# 00A-023_FRDM_Protoboard.net
KiCad netlist of a schematic drawn in EAGLE
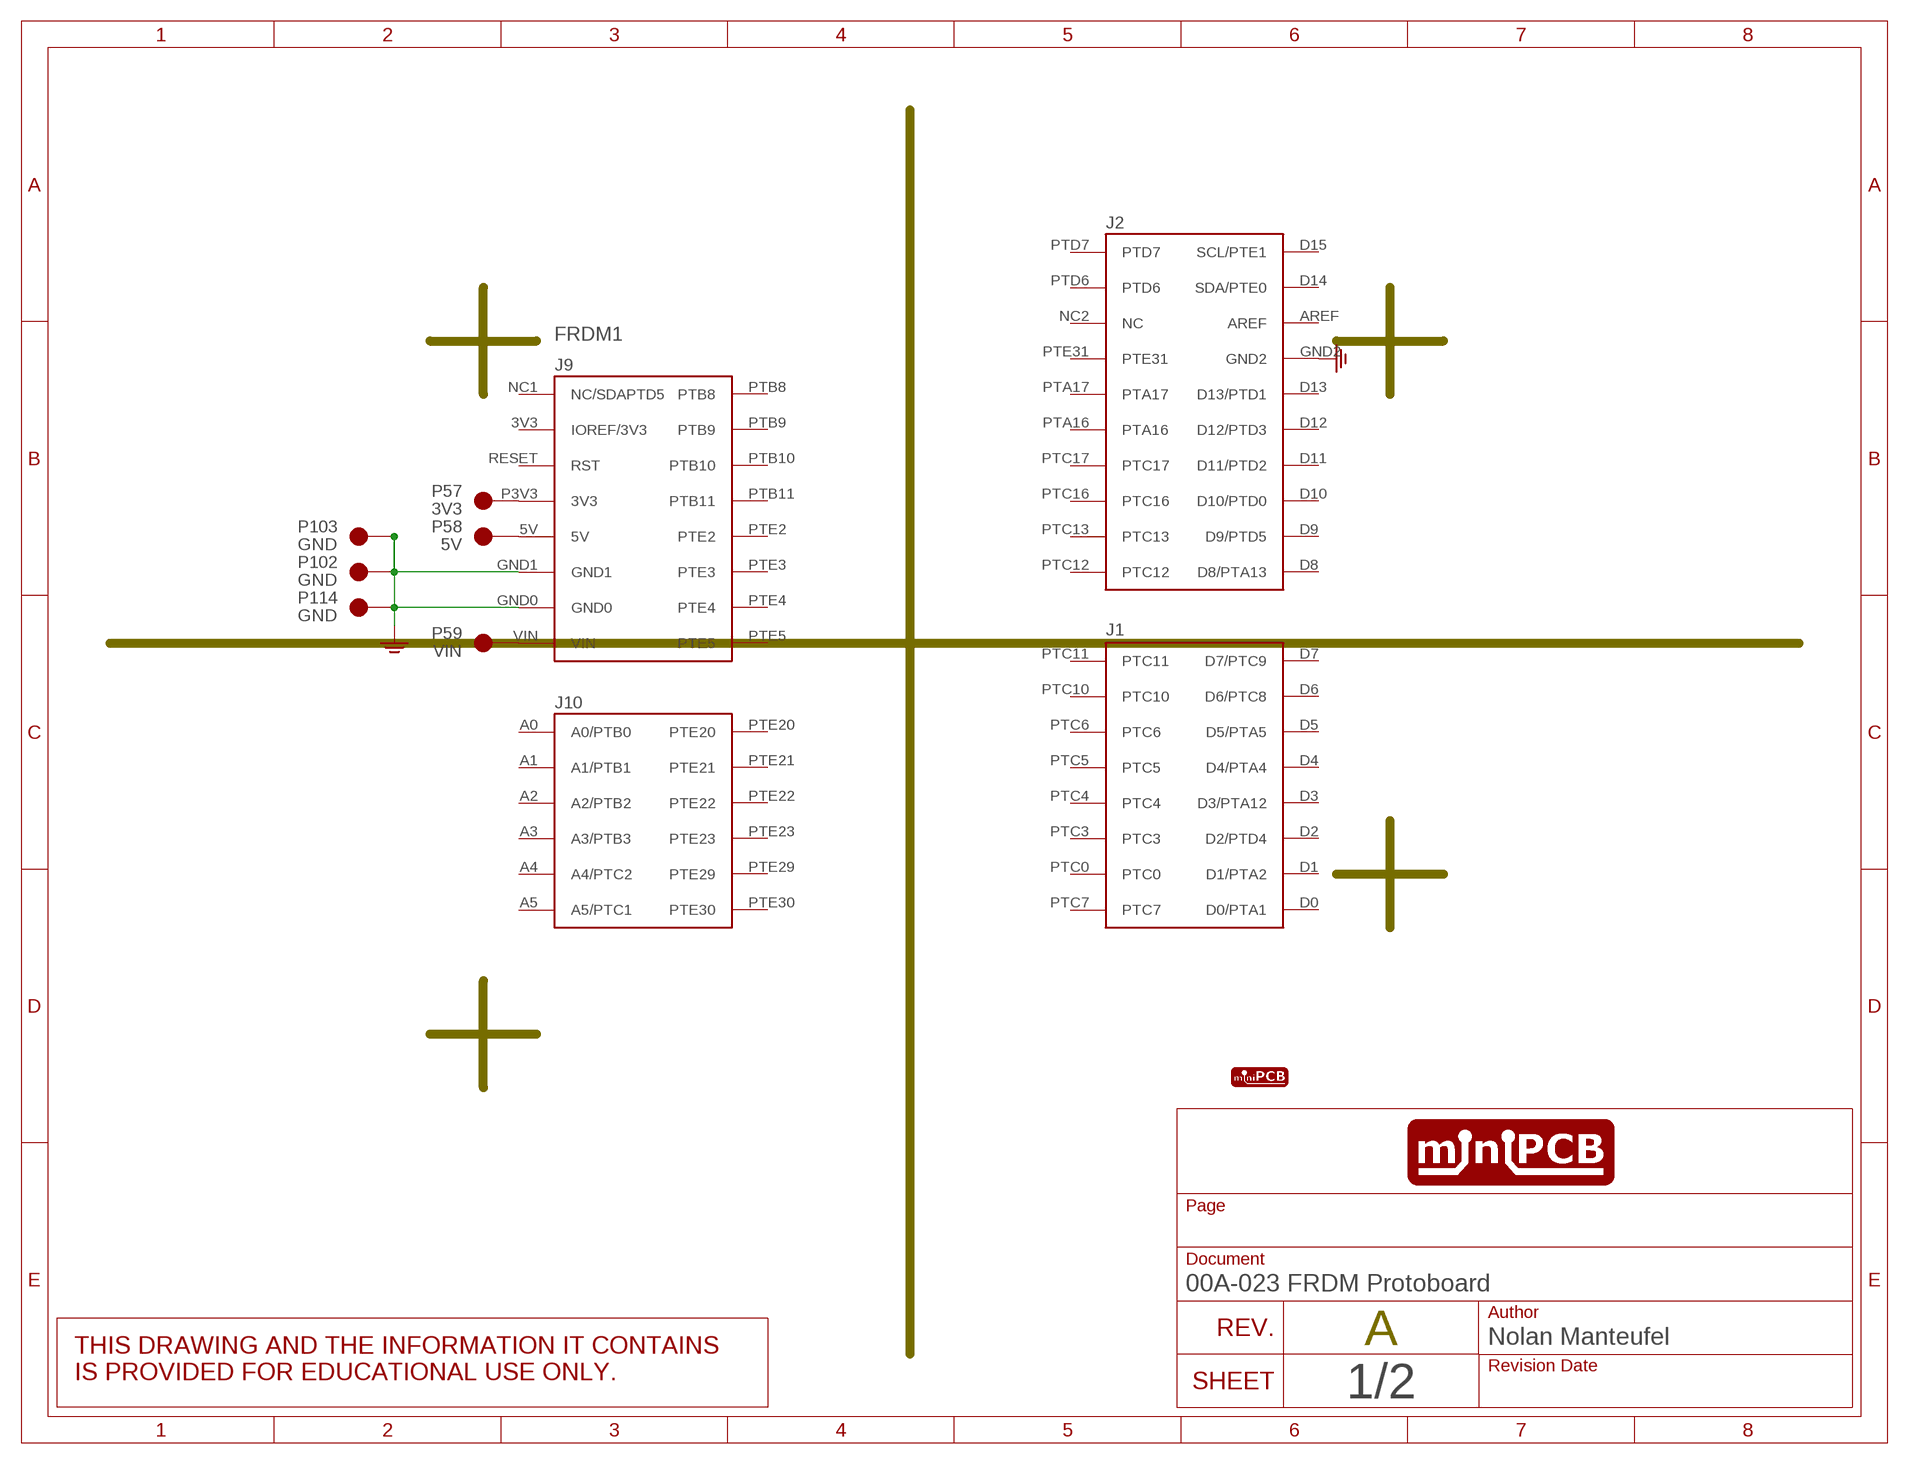
[diagram p0: schematic, sheet 1]
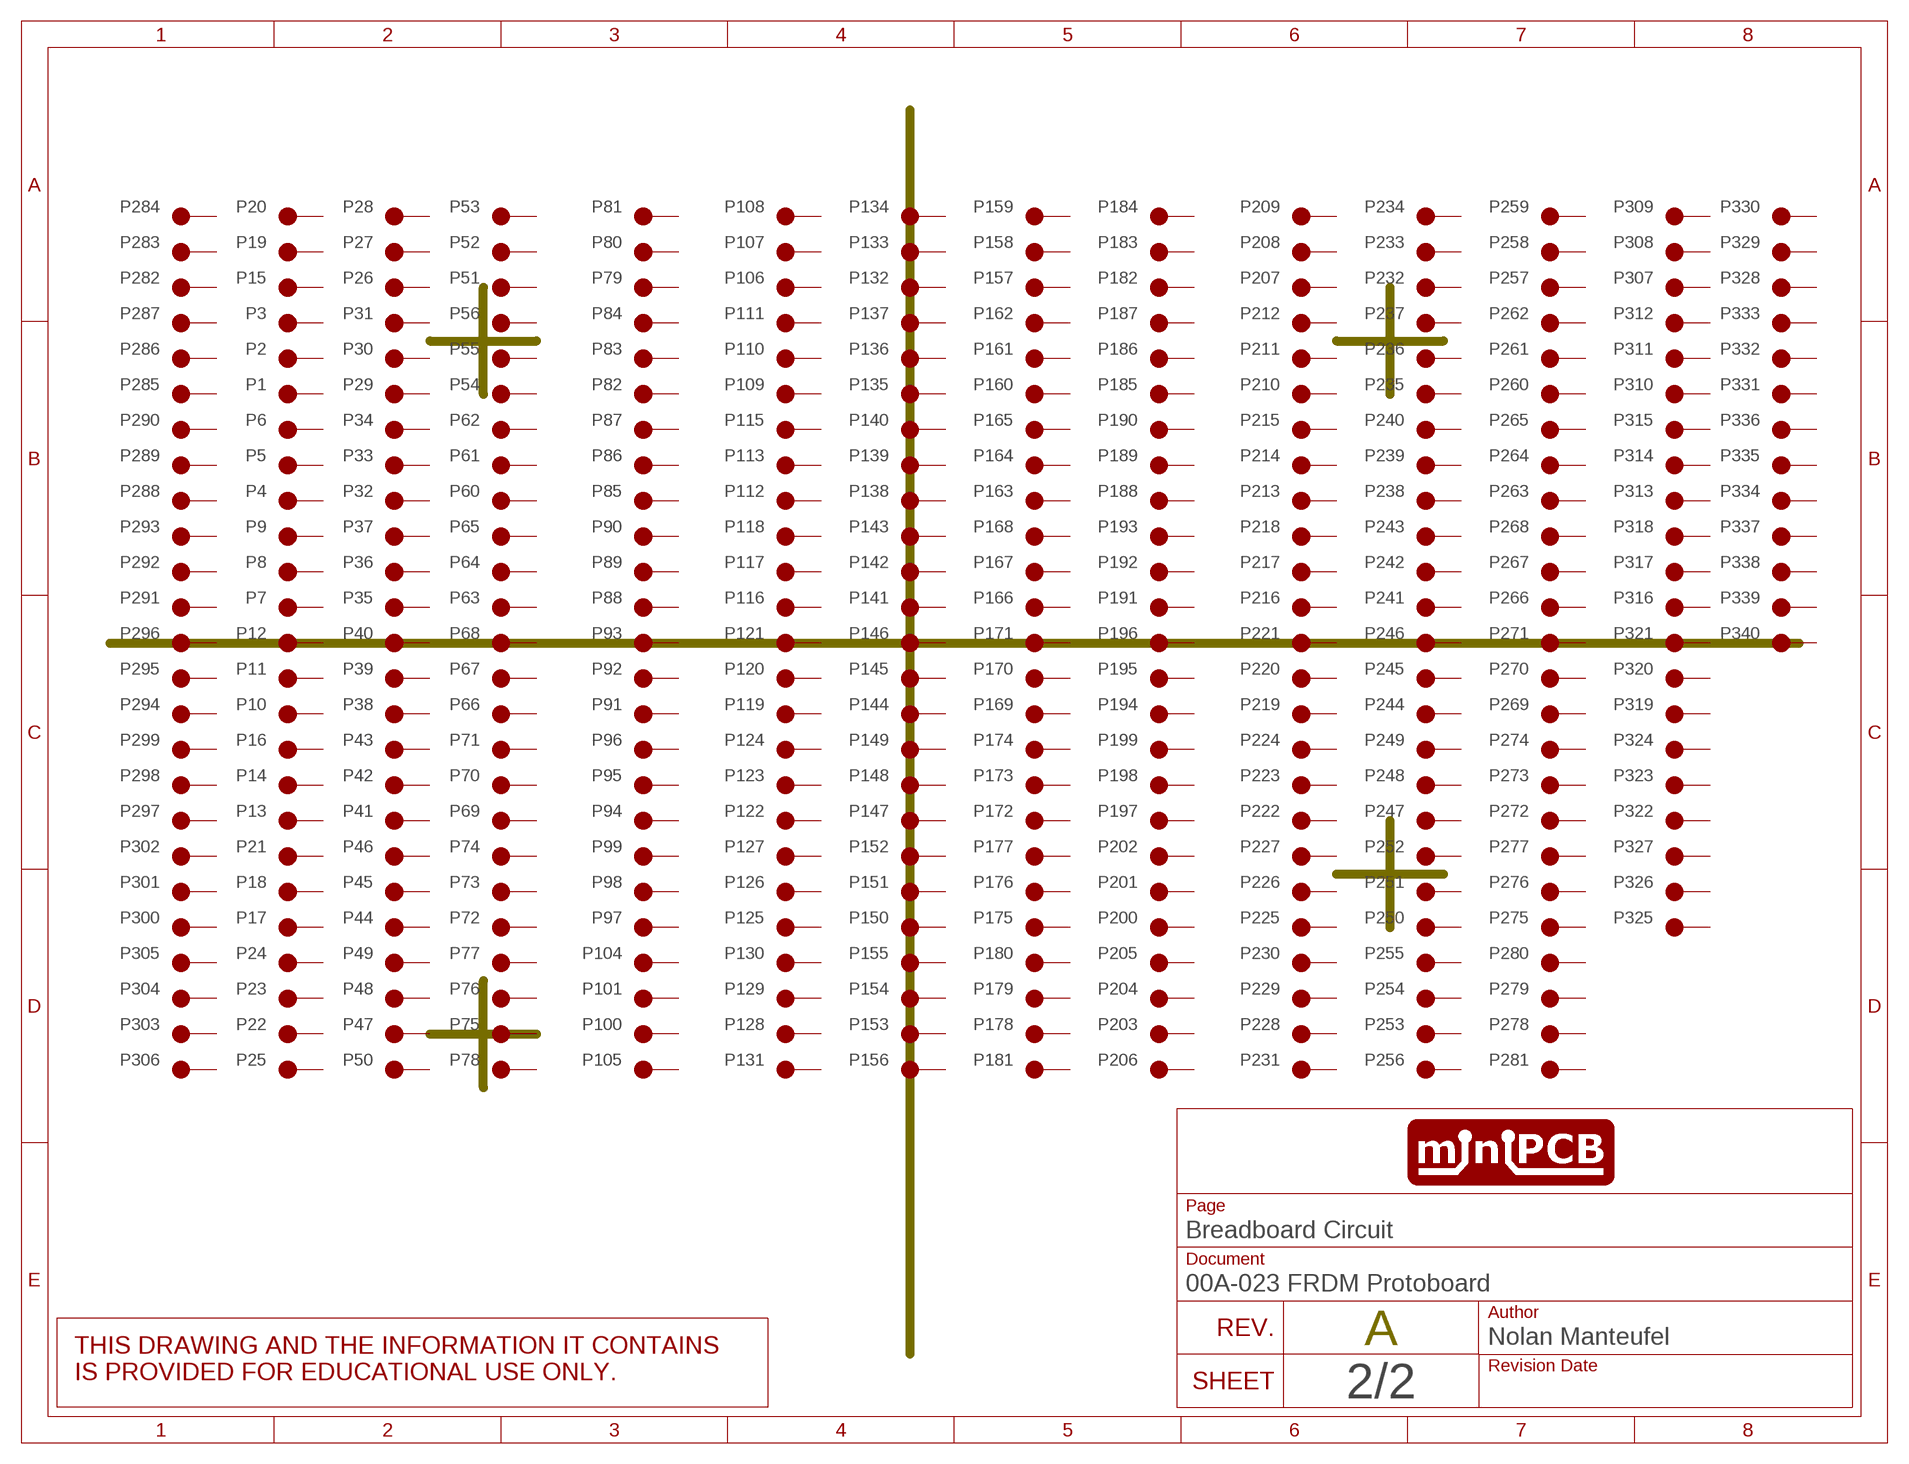
[diagram p1: schematic, sheet 2]

(export (version "E")
  (design (tool "Eeschema 10.0.6"))
  (components
    (comp (ref "P1")
      (value "PINS_11P_VALUE")
      (footprint "eagle-import:PINS_1-1P_VALUE")
      (libsource (lib "eagle-import") (part "PINS_11P_VALUE"))
    )
    (comp (ref "P2")
      (value "PINS_11P_VALUE")
      (footprint "eagle-import:PINS_1-1P_VALUE")
      (libsource (lib "eagle-import") (part "PINS_11P_VALUE"))
    )
    (comp (ref "P3")
      (value "PINS_11P_VALUE")
      (footprint "eagle-import:PINS_1-1P_VALUE")
      (libsource (lib "eagle-import") (part "PINS_11P_VALUE"))
    )
    (comp (ref "P4")
      (value "PINS_11P_VALUE")
      (footprint "eagle-import:PINS_1-1P_VALUE")
      (libsource (lib "eagle-import") (part "PINS_11P_VALUE"))
    )
    (comp (ref "P5")
      (value "PINS_11P_VALUE")
      (footprint "eagle-import:PINS_1-1P_VALUE")
      (libsource (lib "eagle-import") (part "PINS_11P_VALUE"))
    )
    (comp (ref "P6")
      (value "PINS_11P_VALUE")
      (footprint "eagle-import:PINS_1-1P_VALUE")
      (libsource (lib "eagle-import") (part "PINS_11P_VALUE"))
    )
    (comp (ref "P7")
      (value "PINS_11P_VALUE")
      (footprint "eagle-import:PINS_1-1P_VALUE")
      (libsource (lib "eagle-import") (part "PINS_11P_VALUE"))
    )
    (comp (ref "P8")
      (value "PINS_11P_VALUE")
      (footprint "eagle-import:PINS_1-1P_VALUE")
      (libsource (lib "eagle-import") (part "PINS_11P_VALUE"))
    )
    (comp (ref "P9")
      (value "PINS_11P_VALUE")
      (footprint "eagle-import:PINS_1-1P_VALUE")
      (libsource (lib "eagle-import") (part "PINS_11P_VALUE"))
    )
    (comp (ref "P10")
      (value "PINS_11P_VALUE")
      (footprint "eagle-import:PINS_1-1P_VALUE")
      (libsource (lib "eagle-import") (part "PINS_11P_VALUE"))
    )
    (comp (ref "P11")
      (value "PINS_11P_VALUE")
      (footprint "eagle-import:PINS_1-1P_VALUE")
      (libsource (lib "eagle-import") (part "PINS_11P_VALUE"))
    )
    (comp (ref "P12")
      (value "PINS_11P_VALUE")
      (footprint "eagle-import:PINS_1-1P_VALUE")
      (libsource (lib "eagle-import") (part "PINS_11P_VALUE"))
    )
    (comp (ref "P13")
      (value "PINS_11P_VALUE")
      (footprint "eagle-import:PINS_1-1P_VALUE")
      (libsource (lib "eagle-import") (part "PINS_11P_VALUE"))
    )
    (comp (ref "P14")
      (value "PINS_11P_VALUE")
      (footprint "eagle-import:PINS_1-1P_VALUE")
      (libsource (lib "eagle-import") (part "PINS_11P_VALUE"))
    )
    (comp (ref "P15")
      (value "PINS_11P_VALUE")
      (footprint "eagle-import:PINS_1-1P_VALUE")
      (libsource (lib "eagle-import") (part "PINS_11P_VALUE"))
    )
    (comp (ref "P16")
      (value "PINS_11P_VALUE")
      (footprint "eagle-import:PINS_1-1P_VALUE")
      (libsource (lib "eagle-import") (part "PINS_11P_VALUE"))
    )
    (comp (ref "P17")
      (value "PINS_11P_VALUE")
      (footprint "eagle-import:PINS_1-1P_VALUE")
      (libsource (lib "eagle-import") (part "PINS_11P_VALUE"))
    )
    (comp (ref "P18")
      (value "PINS_11P_VALUE")
      (footprint "eagle-import:PINS_1-1P_VALUE")
      (libsource (lib "eagle-import") (part "PINS_11P_VALUE"))
    )
    (comp (ref "P19")
      (value "PINS_11P_VALUE")
      (footprint "eagle-import:PINS_1-1P_VALUE")
      (libsource (lib "eagle-import") (part "PINS_11P_VALUE"))
    )
    (comp (ref "P20")
      (value "PINS_11P_VALUE")
      (footprint "eagle-import:PINS_1-1P_VALUE")
      (libsource (lib "eagle-import") (part "PINS_11P_VALUE"))
    )
    (comp (ref "P21")
      (value "PINS_11P_VALUE")
      (footprint "eagle-import:PINS_1-1P_VALUE")
      (libsource (lib "eagle-import") (part "PINS_11P_VALUE"))
    )
    (comp (ref "P22")
      (value "PINS_11P_VALUE")
      (footprint "eagle-import:PINS_1-1P_VALUE")
      (libsource (lib "eagle-import") (part "PINS_11P_VALUE"))
    )
    (comp (ref "P23")
      (value "PINS_11P_VALUE")
      (footprint "eagle-import:PINS_1-1P_VALUE")
      (libsource (lib "eagle-import") (part "PINS_11P_VALUE"))
    )
    (comp (ref "P24")
      (value "PINS_11P_VALUE")
      (footprint "eagle-import:PINS_1-1P_VALUE")
      (libsource (lib "eagle-import") (part "PINS_11P_VALUE"))
    )
    (comp (ref "P25")
      (value "PINS_11P_VALUE")
      (footprint "eagle-import:PINS_1-1P_VALUE")
      (libsource (lib "eagle-import") (part "PINS_11P_VALUE"))
    )
    (comp (ref "P26")
      (value "PINS_11P_VALUE")
      (footprint "eagle-import:PINS_1-1P_VALUE")
      (libsource (lib "eagle-import") (part "PINS_11P_VALUE"))
    )
    (comp (ref "P27")
      (value "PINS_11P_VALUE")
      (footprint "eagle-import:PINS_1-1P_VALUE")
      (libsource (lib "eagle-import") (part "PINS_11P_VALUE"))
    )
    (comp (ref "P28")
      (value "PINS_11P_VALUE")
      (footprint "eagle-import:PINS_1-1P_VALUE")
      (libsource (lib "eagle-import") (part "PINS_11P_VALUE"))
    )
    (comp (ref "P29")
      (value "PINS_11P_VALUE")
      (footprint "eagle-import:PINS_1-1P_VALUE")
      (libsource (lib "eagle-import") (part "PINS_11P_VALUE"))
    )
    (comp (ref "P30")
      (value "PINS_11P_VALUE")
      (footprint "eagle-import:PINS_1-1P_VALUE")
      (libsource (lib "eagle-import") (part "PINS_11P_VALUE"))
    )
    (comp (ref "P31")
      (value "PINS_11P_VALUE")
      (footprint "eagle-import:PINS_1-1P_VALUE")
      (libsource (lib "eagle-import") (part "PINS_11P_VALUE"))
    )
    (comp (ref "P32")
      (value "PINS_11P_VALUE")
      (footprint "eagle-import:PINS_1-1P_VALUE")
      (libsource (lib "eagle-import") (part "PINS_11P_VALUE"))
    )
    (comp (ref "P33")
      (value "PINS_11P_VALUE")
      (footprint "eagle-import:PINS_1-1P_VALUE")
      (libsource (lib "eagle-import") (part "PINS_11P_VALUE"))
    )
    (comp (ref "P34")
      (value "PINS_11P_VALUE")
      (footprint "eagle-import:PINS_1-1P_VALUE")
      (libsource (lib "eagle-import") (part "PINS_11P_VALUE"))
    )
    (comp (ref "P35")
      (value "PINS_11P_VALUE")
      (footprint "eagle-import:PINS_1-1P_VALUE")
      (libsource (lib "eagle-import") (part "PINS_11P_VALUE"))
    )
    (comp (ref "P36")
      (value "PINS_11P_VALUE")
      (footprint "eagle-import:PINS_1-1P_VALUE")
      (libsource (lib "eagle-import") (part "PINS_11P_VALUE"))
    )
    (comp (ref "P37")
      (value "PINS_11P_VALUE")
      (footprint "eagle-import:PINS_1-1P_VALUE")
      (libsource (lib "eagle-import") (part "PINS_11P_VALUE"))
    )
    (comp (ref "P38")
      (value "PINS_11P_VALUE")
      (footprint "eagle-import:PINS_1-1P_VALUE")
      (libsource (lib "eagle-import") (part "PINS_11P_VALUE"))
    )
    (comp (ref "P39")
      (value "PINS_11P_VALUE")
      (footprint "eagle-import:PINS_1-1P_VALUE")
      (libsource (lib "eagle-import") (part "PINS_11P_VALUE"))
    )
    (comp (ref "P40")
      (value "PINS_11P_VALUE")
      (footprint "eagle-import:PINS_1-1P_VALUE")
      (libsource (lib "eagle-import") (part "PINS_11P_VALUE"))
    )
    (comp (ref "P41")
      (value "PINS_11P_VALUE")
      (footprint "eagle-import:PINS_1-1P_VALUE")
      (libsource (lib "eagle-import") (part "PINS_11P_VALUE"))
    )
    (comp (ref "P42")
      (value "PINS_11P_VALUE")
      (footprint "eagle-import:PINS_1-1P_VALUE")
      (libsource (lib "eagle-import") (part "PINS_11P_VALUE"))
    )
    (comp (ref "P43")
      (value "PINS_11P_VALUE")
      (footprint "eagle-import:PINS_1-1P_VALUE")
      (libsource (lib "eagle-import") (part "PINS_11P_VALUE"))
    )
    (comp (ref "P44")
      (value "PINS_11P_VALUE")
      (footprint "eagle-import:PINS_1-1P_VALUE")
      (libsource (lib "eagle-import") (part "PINS_11P_VALUE"))
    )
    (comp (ref "P45")
      (value "PINS_11P_VALUE")
      (footprint "eagle-import:PINS_1-1P_VALUE")
      (libsource (lib "eagle-import") (part "PINS_11P_VALUE"))
    )
    (comp (ref "P46")
      (value "PINS_11P_VALUE")
      (footprint "eagle-import:PINS_1-1P_VALUE")
      (libsource (lib "eagle-import") (part "PINS_11P_VALUE"))
    )
    (comp (ref "P47")
      (value "PINS_11P_VALUE")
      (footprint "eagle-import:PINS_1-1P_VALUE")
      (libsource (lib "eagle-import") (part "PINS_11P_VALUE"))
    )
    (comp (ref "P48")
      (value "PINS_11P_VALUE")
      (footprint "eagle-import:PINS_1-1P_VALUE")
      (libsource (lib "eagle-import") (part "PINS_11P_VALUE"))
    )
    (comp (ref "P49")
      (value "PINS_11P_VALUE")
      (footprint "eagle-import:PINS_1-1P_VALUE")
      (libsource (lib "eagle-import") (part "PINS_11P_VALUE"))
    )
    (comp (ref "P50")
      (value "PINS_11P_VALUE")
      (footprint "eagle-import:PINS_1-1P_VALUE")
      (libsource (lib "eagle-import") (part "PINS_11P_VALUE"))
    )
    (comp (ref "P51")
      (value "PINS_11P_VALUE")
      (footprint "eagle-import:PINS_1-1P_VALUE")
      (libsource (lib "eagle-import") (part "PINS_11P_VALUE"))
    )
    (comp (ref "P52")
      (value "PINS_11P_VALUE")
      (footprint "eagle-import:PINS_1-1P_VALUE")
      (libsource (lib "eagle-import") (part "PINS_11P_VALUE"))
    )
    (comp (ref "P53")
      (value "PINS_11P_VALUE")
      (footprint "eagle-import:PINS_1-1P_VALUE")
      (libsource (lib "eagle-import") (part "PINS_11P_VALUE"))
    )
    (comp (ref "P54")
      (value "PINS_11P_VALUE")
      (footprint "eagle-import:PINS_1-1P_VALUE")
      (libsource (lib "eagle-import") (part "PINS_11P_VALUE"))
    )
    (comp (ref "P55")
      (value "PINS_11P_VALUE")
      (footprint "eagle-import:PINS_1-1P_VALUE")
      (libsource (lib "eagle-import") (part "PINS_11P_VALUE"))
    )
    (comp (ref "P56")
      (value "PINS_11P_VALUE")
      (footprint "eagle-import:PINS_1-1P_VALUE")
      (libsource (lib "eagle-import") (part "PINS_11P_VALUE"))
    )
    (comp (ref "P60")
      (value "PINS_11P_VALUE")
      (footprint "eagle-import:PINS_1-1P_VALUE")
      (libsource (lib "eagle-import") (part "PINS_11P_VALUE"))
    )
    (comp (ref "P61")
      (value "PINS_11P_VALUE")
      (footprint "eagle-import:PINS_1-1P_VALUE")
      (libsource (lib "eagle-import") (part "PINS_11P_VALUE"))
    )
    (comp (ref "P62")
      (value "PINS_11P_VALUE")
      (footprint "eagle-import:PINS_1-1P_VALUE")
      (libsource (lib "eagle-import") (part "PINS_11P_VALUE"))
    )
    (comp (ref "P63")
      (value "PINS_11P_VALUE")
      (footprint "eagle-import:PINS_1-1P_VALUE")
      (libsource (lib "eagle-import") (part "PINS_11P_VALUE"))
    )
    (comp (ref "P64")
      (value "PINS_11P_VALUE")
      (footprint "eagle-import:PINS_1-1P_VALUE")
      (libsource (lib "eagle-import") (part "PINS_11P_VALUE"))
    )
    (comp (ref "P65")
      (value "PINS_11P_VALUE")
      (footprint "eagle-import:PINS_1-1P_VALUE")
      (libsource (lib "eagle-import") (part "PINS_11P_VALUE"))
    )
    (comp (ref "P66")
      (value "PINS_11P_VALUE")
      (footprint "eagle-import:PINS_1-1P_VALUE")
      (libsource (lib "eagle-import") (part "PINS_11P_VALUE"))
    )
    (comp (ref "P67")
      (value "PINS_11P_VALUE")
      (footprint "eagle-import:PINS_1-1P_VALUE")
      (libsource (lib "eagle-import") (part "PINS_11P_VALUE"))
    )
    (comp (ref "P68")
      (value "PINS_11P_VALUE")
      (footprint "eagle-import:PINS_1-1P_VALUE")
      (libsource (lib "eagle-import") (part "PINS_11P_VALUE"))
    )
    (comp (ref "P69")
      (value "PINS_11P_VALUE")
      (footprint "eagle-import:PINS_1-1P_VALUE")
      (libsource (lib "eagle-import") (part "PINS_11P_VALUE"))
    )
    (comp (ref "P70")
      (value "PINS_11P_VALUE")
      (footprint "eagle-import:PINS_1-1P_VALUE")
      (libsource (lib "eagle-import") (part "PINS_11P_VALUE"))
    )
    (comp (ref "P71")
      (value "PINS_11P_VALUE")
      (footprint "eagle-import:PINS_1-1P_VALUE")
      (libsource (lib "eagle-import") (part "PINS_11P_VALUE"))
    )
    (comp (ref "P72")
      (value "PINS_11P_VALUE")
      (footprint "eagle-import:PINS_1-1P_VALUE")
      (libsource (lib "eagle-import") (part "PINS_11P_VALUE"))
    )
    (comp (ref "P73")
      (value "PINS_11P_VALUE")
      (footprint "eagle-import:PINS_1-1P_VALUE")
      (libsource (lib "eagle-import") (part "PINS_11P_VALUE"))
    )
    (comp (ref "P74")
      (value "PINS_11P_VALUE")
      (footprint "eagle-import:PINS_1-1P_VALUE")
      (libsource (lib "eagle-import") (part "PINS_11P_VALUE"))
    )
    (comp (ref "P75")
      (value "PINS_11P_VALUE")
      (footprint "eagle-import:PINS_1-1P_VALUE")
      (libsource (lib "eagle-import") (part "PINS_11P_VALUE"))
    )
    (comp (ref "P76")
      (value "PINS_11P_VALUE")
      (footprint "eagle-import:PINS_1-1P_VALUE")
      (libsource (lib "eagle-import") (part "PINS_11P_VALUE"))
    )
    (comp (ref "P77")
      (value "PINS_11P_VALUE")
      (footprint "eagle-import:PINS_1-1P_VALUE")
      (libsource (lib "eagle-import") (part "PINS_11P_VALUE"))
    )
    (comp (ref "P78")
      (value "PINS_11P_VALUE")
      (footprint "eagle-import:PINS_1-1P_VALUE")
      (libsource (lib "eagle-import") (part "PINS_11P_VALUE"))
    )
    (comp (ref "P79")
      (value "PINS_11P_VALUE")
      (footprint "eagle-import:PINS_1-1P_VALUE")
      (libsource (lib "eagle-import") (part "PINS_11P_VALUE"))
    )
    (comp (ref "P80")
      (value "PINS_11P_VALUE")
      (footprint "eagle-import:PINS_1-1P_VALUE")
      (libsource (lib "eagle-import") (part "PINS_11P_VALUE"))
    )
    (comp (ref "P81")
      (value "PINS_11P_VALUE")
      (footprint "eagle-import:PINS_1-1P_VALUE")
      (libsource (lib "eagle-import") (part "PINS_11P_VALUE"))
    )
    (comp (ref "P82")
      (value "PINS_11P_VALUE")
      (footprint "eagle-import:PINS_1-1P_VALUE")
      (libsource (lib "eagle-import") (part "PINS_11P_VALUE"))
    )
    (comp (ref "P83")
      (value "PINS_11P_VALUE")
      (footprint "eagle-import:PINS_1-1P_VALUE")
      (libsource (lib "eagle-import") (part "PINS_11P_VALUE"))
    )
    (comp (ref "P84")
      (value "PINS_11P_VALUE")
      (footprint "eagle-import:PINS_1-1P_VALUE")
      (libsource (lib "eagle-import") (part "PINS_11P_VALUE"))
    )
    (comp (ref "P85")
      (value "PINS_11P_VALUE")
      (footprint "eagle-import:PINS_1-1P_VALUE")
      (libsource (lib "eagle-import") (part "PINS_11P_VALUE"))
    )
    (comp (ref "P86")
      (value "PINS_11P_VALUE")
      (footprint "eagle-import:PINS_1-1P_VALUE")
      (libsource (lib "eagle-import") (part "PINS_11P_VALUE"))
    )
    (comp (ref "P87")
      (value "PINS_11P_VALUE")
      (footprint "eagle-import:PINS_1-1P_VALUE")
      (libsource (lib "eagle-import") (part "PINS_11P_VALUE"))
    )
    (comp (ref "P88")
      (value "PINS_11P_VALUE")
      (footprint "eagle-import:PINS_1-1P_VALUE")
      (libsource (lib "eagle-import") (part "PINS_11P_VALUE"))
    )
    (comp (ref "P89")
      (value "PINS_11P_VALUE")
      (footprint "eagle-import:PINS_1-1P_VALUE")
      (libsource (lib "eagle-import") (part "PINS_11P_VALUE"))
    )
    (comp (ref "P90")
      (value "PINS_11P_VALUE")
      (footprint "eagle-import:PINS_1-1P_VALUE")
      (libsource (lib "eagle-import") (part "PINS_11P_VALUE"))
    )
    (comp (ref "P91")
      (value "PINS_11P_VALUE")
      (footprint "eagle-import:PINS_1-1P_VALUE")
      (libsource (lib "eagle-import") (part "PINS_11P_VALUE"))
    )
    (comp (ref "P92")
      (value "PINS_11P_VALUE")
      (footprint "eagle-import:PINS_1-1P_VALUE")
      (libsource (lib "eagle-import") (part "PINS_11P_VALUE"))
    )
    (comp (ref "P93")
      (value "PINS_11P_VALUE")
      (footprint "eagle-import:PINS_1-1P_VALUE")
      (libsource (lib "eagle-import") (part "PINS_11P_VALUE"))
    )
    (comp (ref "P94")
      (value "PINS_11P_VALUE")
      (footprint "eagle-import:PINS_1-1P_VALUE")
      (libsource (lib "eagle-import") (part "PINS_11P_VALUE"))
    )
    (comp (ref "P95")
      (value "PINS_11P_VALUE")
      (footprint "eagle-import:PINS_1-1P_VALUE")
      (libsource (lib "eagle-import") (part "PINS_11P_VALUE"))
    )
    (comp (ref "P96")
      (value "PINS_11P_VALUE")
      (footprint "eagle-import:PINS_1-1P_VALUE")
      (libsource (lib "eagle-import") (part "PINS_11P_VALUE"))
    )
    (comp (ref "P97")
      (value "PINS_11P_VALUE")
      (footprint "eagle-import:PINS_1-1P_VALUE")
      (libsource (lib "eagle-import") (part "PINS_11P_VALUE"))
    )
    (comp (ref "P98")
      (value "PINS_11P_VALUE")
      (footprint "eagle-import:PINS_1-1P_VALUE")
      (libsource (lib "eagle-import") (part "PINS_11P_VALUE"))
    )
    (comp (ref "P99")
      (value "PINS_11P_VALUE")
      (footprint "eagle-import:PINS_1-1P_VALUE")
      (libsource (lib "eagle-import") (part "PINS_11P_VALUE"))
    )
    (comp (ref "P100")
      (value "PINS_11P_VALUE")
      (footprint "eagle-import:PINS_1-1P_VALUE")
      (libsource (lib "eagle-import") (part "PINS_11P_VALUE"))
    )
    (comp (ref "P101")
      (value "PINS_11P_VALUE")
      (footprint "eagle-import:PINS_1-1P_VALUE")
      (libsource (lib "eagle-import") (part "PINS_11P_VALUE"))
    )
    (comp (ref "P104")
      (value "PINS_11P_VALUE")
      (footprint "eagle-import:PINS_1-1P_VALUE")
      (libsource (lib "eagle-import") (part "PINS_11P_VALUE"))
    )
    (comp (ref "P105")
      (value "PINS_11P_VALUE")
      (footprint "eagle-import:PINS_1-1P_VALUE")
      (libsource (lib "eagle-import") (part "PINS_11P_VALUE"))
    )
    (comp (ref "P106")
      (value "PINS_11P_VALUE")
      (footprint "eagle-import:PINS_1-1P_VALUE")
      (libsource (lib "eagle-import") (part "PINS_11P_VALUE"))
    )
    (comp (ref "P107")
      (value "PINS_11P_VALUE")
      (footprint "eagle-import:PINS_1-1P_VALUE")
      (libsource (lib "eagle-import") (part "PINS_11P_VALUE"))
    )
    (comp (ref "P108")
      (value "PINS_11P_VALUE")
      (footprint "eagle-import:PINS_1-1P_VALUE")
      (libsource (lib "eagle-import") (part "PINS_11P_VALUE"))
    )
    (comp (ref "P109")
      (value "PINS_11P_VALUE")
      (footprint "eagle-import:PINS_1-1P_VALUE")
      (libsource (lib "eagle-import") (part "PINS_11P_VALUE"))
    )
    (comp (ref "P110")
      (value "PINS_11P_VALUE")
      (footprint "eagle-import:PINS_1-1P_VALUE")
      (libsource (lib "eagle-import") (part "PINS_11P_VALUE"))
    )
    (comp (ref "P111")
      (value "PINS_11P_VALUE")
      (footprint "eagle-import:PINS_1-1P_VALUE")
      (libsource (lib "eagle-import") (part "PINS_11P_VALUE"))
    )
    (comp (ref "P112")
      (value "PINS_11P_VALUE")
      (footprint "eagle-import:PINS_1-1P_VALUE")
      (libsource (lib "eagle-import") (part "PINS_11P_VALUE"))
    )
    (comp (ref "P113")
      (value "PINS_11P_VALUE")
      (footprint "eagle-import:PINS_1-1P_VALUE")
      (libsource (lib "eagle-import") (part "PINS_11P_VALUE"))
    )
    (comp (ref "P115")
      (value "PINS_11P_VALUE")
      (footprint "eagle-import:PINS_1-1P_VALUE")
      (libsource (lib "eagle-import") (part "PINS_11P_VALUE"))
    )
    (comp (ref "P116")
      (value "PINS_11P_VALUE")
      (footprint "eagle-import:PINS_1-1P_VALUE")
      (libsource (lib "eagle-import") (part "PINS_11P_VALUE"))
    )
    (comp (ref "P117")
      (value "PINS_11P_VALUE")
      (footprint "eagle-import:PINS_1-1P_VALUE")
      (libsource (lib "eagle-import") (part "PINS_11P_VALUE"))
    )
    (comp (ref "P118")
      (value "PINS_11P_VALUE")
      (footprint "eagle-import:PINS_1-1P_VALUE")
      (libsource (lib "eagle-import") (part "PINS_11P_VALUE"))
    )
    (comp (ref "P119")
      (value "PINS_11P_VALUE")
      (footprint "eagle-import:PINS_1-1P_VALUE")
      (libsource (lib "eagle-import") (part "PINS_11P_VALUE"))
    )
    (comp (ref "P120")
      (value "PINS_11P_VALUE")
      (footprint "eagle-import:PINS_1-1P_VALUE")
      (libsource (lib "eagle-import") (part "PINS_11P_VALUE"))
    )
    (comp (ref "P121")
      (value "PINS_11P_VALUE")
      (footprint "eagle-import:PINS_1-1P_VALUE")
      (libsource (lib "eagle-import") (part "PINS_11P_VALUE"))
    )
    (comp (ref "P122")
      (value "PINS_11P_VALUE")
      (footprint "eagle-import:PINS_1-1P_VALUE")
      (libsource (lib "eagle-import") (part "PINS_11P_VALUE"))
    )
    (comp (ref "P123")
      (value "PINS_11P_VALUE")
      (footprint "eagle-import:PINS_1-1P_VALUE")
      (libsource (lib "eagle-import") (part "PINS_11P_VALUE"))
    )
    (comp (ref "P124")
      (value "PINS_11P_VALUE")
      (footprint "eagle-import:PINS_1-1P_VALUE")
      (libsource (lib "eagle-import") (part "PINS_11P_VALUE"))
    )
    (comp (ref "P125")
      (value "PINS_11P_VALUE")
      (footprint "eagle-import:PINS_1-1P_VALUE")
      (libsource (lib "eagle-import") (part "PINS_11P_VALUE"))
    )
    (comp (ref "P126")
      (value "PINS_11P_VALUE")
      (footprint "eagle-import:PINS_1-1P_VALUE")
      (libsource (lib "eagle-import") (part "PINS_11P_VALUE"))
    )
    (comp (ref "P127")
      (value "PINS_11P_VALUE")
      (footprint "eagle-import:PINS_1-1P_VALUE")
      (libsource (lib "eagle-import") (part "PINS_11P_VALUE"))
    )
    (comp (ref "P128")
      (value "PINS_11P_VALUE")
      (footprint "eagle-import:PINS_1-1P_VALUE")
      (libsource (lib "eagle-import") (part "PINS_11P_VALUE"))
    )
    (comp (ref "P129")
      (value "PINS_11P_VALUE")
      (footprint "eagle-import:PINS_1-1P_VALUE")
      (libsource (lib "eagle-import") (part "PINS_11P_VALUE"))
    )
    (comp (ref "P130")
      (value "PINS_11P_VALUE")
      (footprint "eagle-import:PINS_1-1P_VALUE")
      (libsource (lib "eagle-import") (part "PINS_11P_VALUE"))
    )
    (comp (ref "P131")
      (value "PINS_11P_VALUE")
      (footprint "eagle-import:PINS_1-1P_VALUE")
      (libsource (lib "eagle-import") (part "PINS_11P_VALUE"))
    )
    (comp (ref "P132")
      (value "PINS_11P_VALUE")
      (footprint "eagle-import:PINS_1-1P_VALUE")
      (libsource (lib "eagle-import") (part "PINS_11P_VALUE"))
    )
    (comp (ref "P133")
      (value "PINS_11P_VALUE")
      (footprint "eagle-import:PINS_1-1P_VALUE")
      (libsource (lib "eagle-import") (part "PINS_11P_VALUE"))
    )
    (comp (ref "P134")
      (value "PINS_11P_VALUE")
      (footprint "eagle-import:PINS_1-1P_VALUE")
      (libsource (lib "eagle-import") (part "PINS_11P_VALUE"))
    )
    (comp (ref "P135")
      (value "PINS_11P_VALUE")
      (footprint "eagle-import:PINS_1-1P_VALUE")
      (libsource (lib "eagle-import") (part "PINS_11P_VALUE"))
    )
    (comp (ref "P136")
      (value "PINS_11P_VALUE")
      (footprint "eagle-import:PINS_1-1P_VALUE")
      (libsource (lib "eagle-import") (part "PINS_11P_VALUE"))
    )
    (comp (ref "P137")
      (value "PINS_11P_VALUE")
      (footprint "eagle-import:PINS_1-1P_VALUE")
      (libsource (lib "eagle-import") (part "PINS_11P_VALUE"))
    )
    (comp (ref "P138")
      (value "PINS_11P_VALUE")
      (footprint "eagle-import:PINS_1-1P_VALUE")
      (libsource (lib "eagle-import") (part "PINS_11P_VALUE"))
    )
    (comp (ref "P139")
      (value "PINS_11P_VALUE")
      (footprint "eagle-import:PINS_1-1P_VALUE")
      (libsource (lib "eagle-import") (part "PINS_11P_VALUE"))
    )
    (comp (ref "P140")
      (value "PINS_11P_VALUE")
      (footprint "eagle-import:PINS_1-1P_VALUE")
      (libsource (lib "eagle-import") (part "PINS_11P_VALUE"))
    )
    (comp (ref "P141")
      (value "PINS_11P_VALUE")
      (footprint "eagle-import:PINS_1-1P_VALUE")
      (libsource (lib "eagle-import") (part "PINS_11P_VALUE"))
    )
    (comp (ref "P142")
      (value "PINS_11P_VALUE")
      (footprint "eagle-import:PINS_1-1P_VALUE")
      (libsource (lib "eagle-import") (part "PINS_11P_VALUE"))
    )
    (comp (ref "P143")
      (value "PINS_11P_VALUE")
      (footprint "eagle-import:PINS_1-1P_VALUE")
      (libsource (lib "eagle-import") (part "PINS_11P_VALUE"))
    )
    (comp (ref "P144")
      (value "PINS_11P_VALUE")
      (footprint "eagle-import:PINS_1-1P_VALUE")
      (libsource (lib "eagle-import") (part "PINS_11P_VALUE"))
    )
    (comp (ref "P145")
      (value "PINS_11P_VALUE")
      (footprint "eagle-import:PINS_1-1P_VALUE")
      (libsource (lib "eagle-import") (part "PINS_11P_VALUE"))
    )
    (comp (ref "P146")
      (value "PINS_11P_VALUE")
      (footprint "eagle-import:PINS_1-1P_VALUE")
      (libsource (lib "eagle-import") (part "PINS_11P_VALUE"))
    )
    (comp (ref "P147")
      (value "PINS_11P_VALUE")
      (footprint "eagle-import:PINS_1-1P_VALUE")
      (libsource (lib "eagle-import") (part "PINS_11P_VALUE"))
    )
    (comp (ref "P148")
      (value "PINS_11P_VALUE")
      (footprint "eagle-import:PINS_1-1P_VALUE")
      (libsource (lib "eagle-import") (part "PINS_11P_VALUE"))
    )
    (comp (ref "P149")
      (value "PINS_11P_VALUE")
      (footprint "eagle-import:PINS_1-1P_VALUE")
      (libsource (lib "eagle-import") (part "PINS_11P_VALUE"))
    )
    (comp (ref "P150")
      (value "PINS_11P_VALUE")
      (footprint "eagle-import:PINS_1-1P_VALUE")
      (libsource (lib "eagle-import") (part "PINS_11P_VALUE"))
    )
    (comp (ref "P151")
      (value "PINS_11P_VALUE")
      (footprint "eagle-import:PINS_1-1P_VALUE")
      (libsource (lib "eagle-import") (part "PINS_11P_VALUE"))
    )
    (comp (ref "P152")
      (value "PINS_11P_VALUE")
      (footprint "eagle-import:PINS_1-1P_VALUE")
      (libsource (lib "eagle-import") (part "PINS_11P_VALUE"))
    )
    (comp (ref "P153")
      (value "PINS_11P_VALUE")
      (footprint "eagle-import:PINS_1-1P_VALUE")
      (libsource (lib "eagle-import") (part "PINS_11P_VALUE"))
    )
    (comp (ref "P154")
      (value "PINS_11P_VALUE")
      (footprint "eagle-import:PINS_1-1P_VALUE")
      (libsource (lib "eagle-import") (part "PINS_11P_VALUE"))
    )
    (comp (ref "P155")
      (value "PINS_11P_VALUE")
      (footprint "eagle-import:PINS_1-1P_VALUE")
      (libsource (lib "eagle-import") (part "PINS_11P_VALUE"))
    )
    (comp (ref "P156")
      (value "PINS_11P_VALUE")
      (footprint "eagle-import:PINS_1-1P_VALUE")
      (libsource (lib "eagle-import") (part "PINS_11P_VALUE"))
    )
    (comp (ref "P157")
      (value "PINS_11P_VALUE")
      (footprint "eagle-import:PINS_1-1P_VALUE")
      (libsource (lib "eagle-import") (part "PINS_11P_VALUE"))
    )
    (comp (ref "P158")
      (value "PINS_11P_VALUE")
      (footprint "eagle-import:PINS_1-1P_VALUE")
      (libsource (lib "eagle-import") (part "PINS_11P_VALUE"))
    )
    (comp (ref "P159")
      (value "PINS_11P_VALUE")
      (footprint "eagle-import:PINS_1-1P_VALUE")
      (libsource (lib "eagle-import") (part "PINS_11P_VALUE"))
    )
    (comp (ref "P160")
      (value "PINS_11P_VALUE")
      (footprint "eagle-import:PINS_1-1P_VALUE")
      (libsource (lib "eagle-import") (part "PINS_11P_VALUE"))
    )
    (comp (ref "P161")
      (value "PINS_11P_VALUE")
      (footprint "eagle-import:PINS_1-1P_VALUE")
      (libsource (lib "eagle-import") (part "PINS_11P_VALUE"))
    )
    (comp (ref "P162")
      (value "PINS_11P_VALUE")
      (footprint "eagle-import:PINS_1-1P_VALUE")
      (libsource (lib "eagle-import") (part "PINS_11P_VALUE"))
    )
    (comp (ref "P163")
      (value "PINS_11P_VALUE")
      (footprint "eagle-import:PINS_1-1P_VALUE")
      (libsource (lib "eagle-import") (part "PINS_11P_VALUE"))
    )
    (comp (ref "P164")
      (value "PINS_11P_VALUE")
      (footprint "eagle-import:PINS_1-1P_VALUE")
      (libsource (lib "eagle-import") (part "PINS_11P_VALUE"))
    )
    (comp (ref "P165")
      (value "PINS_11P_VALUE")
      (footprint "eagle-import:PINS_1-1P_VALUE")
      (libsource (lib "eagle-import") (part "PINS_11P_VALUE"))
    )
    (comp (ref "P166")
      (value "PINS_11P_VALUE")
      (footprint "eagle-import:PINS_1-1P_VALUE")
      (libsource (lib "eagle-import") (part "PINS_11P_VALUE"))
    )
    (comp (ref "P167")
      (value "PINS_11P_VALUE")
      (footprint "eagle-import:PINS_1-1P_VALUE")
      (libsource (lib "eagle-import") (part "PINS_11P_VALUE"))
    )
    (comp (ref "P168")
      (value "PINS_11P_VALUE")
      (footprint "eagle-import:PINS_1-1P_VALUE")
      (libsource (lib "eagle-import") (part "PINS_11P_VALUE"))
    )
    (comp (ref "P169")
      (value "PINS_11P_VALUE")
      (footprint "eagle-import:PINS_1-1P_VALUE")
      (libsource (lib "eagle-import") (part "PINS_11P_VALUE"))
    )
    (comp (ref "P170")
      (value "PINS_11P_VALUE")
      (footprint "eagle-import:PINS_1-1P_VALUE")
      (libsource (lib "eagle-import") (part "PINS_11P_VALUE"))
    )
    (comp (ref "P171")
      (value "PINS_11P_VALUE")
      (footprint "eagle-import:PINS_1-1P_VALUE")
      (libsource (lib "eagle-import") (part "PINS_11P_VALUE"))
    )
    (comp (ref "P172")
      (value "PINS_11P_VALUE")
      (footprint "eagle-import:PINS_1-1P_VALUE")
      (libsource (lib "eagle-import") (part "PINS_11P_VALUE"))
    )
    (comp (ref "P173")
      (value "PINS_11P_VALUE")
      (footprint "eagle-import:PINS_1-1P_VALUE")
      (libsource (lib "eagle-import") (part "PINS_11P_VALUE"))
    )
    (comp (ref "P174")
      (value "PINS_11P_VALUE")
      (footprint "eagle-import:PINS_1-1P_VALUE")
      (libsource (lib "eagle-import") (part "PINS_11P_VALUE"))
    )
    (comp (ref "P175")
      (value "PINS_11P_VALUE")
      (footprint "eagle-import:PINS_1-1P_VALUE")
      (libsource (lib "eagle-import") (part "PINS_11P_VALUE"))
    )
    (comp (ref "P176")
      (value "PINS_11P_VALUE")
      (footprint "eagle-import:PINS_1-1P_VALUE")
      (libsource (lib "eagle-import") (part "PINS_11P_VALUE"))
    )
    (comp (ref "P177")
      (value "PINS_11P_VALUE")
      (footprint "eagle-import:PINS_1-1P_VALUE")
      (libsource (lib "eagle-import") (part "PINS_11P_VALUE"))
    )
    (comp (ref "P178")
      (value "PINS_11P_VALUE")
      (footprint "eagle-import:PINS_1-1P_VALUE")
      (libsource (lib "eagle-import") (part "PINS_11P_VALUE"))
    )
    (comp (ref "P179")
      (value "PINS_11P_VALUE")
      (footprint "eagle-import:PINS_1-1P_VALUE")
      (libsource (lib "eagle-import") (part "PINS_11P_VALUE"))
    )
    (comp (ref "P180")
      (value "PINS_11P_VALUE")
      (footprint "eagle-import:PINS_1-1P_VALUE")
      (libsource (lib "eagle-import") (part "PINS_11P_VALUE"))
    )
    (comp (ref "P181")
      (value "PINS_11P_VALUE")
      (footprint "eagle-import:PINS_1-1P_VALUE")
      (libsource (lib "eagle-import") (part "PINS_11P_VALUE"))
    )
    (comp (ref "P182")
      (value "PINS_11P_VALUE")
      (footprint "eagle-import:PINS_1-1P_VALUE")
      (libsource (lib "eagle-import") (part "PINS_11P_VALUE"))
    )
    (comp (ref "P183")
      (value "PINS_11P_VALUE")
      (footprint "eagle-import:PINS_1-1P_VALUE")
      (libsource (lib "eagle-import") (part "PINS_11P_VALUE"))
    )
    (comp (ref "P184")
      (value "PINS_11P_VALUE")
      (footprint "eagle-import:PINS_1-1P_VALUE")
      (libsource (lib "eagle-import") (part "PINS_11P_VALUE"))
    )
    (comp (ref "P185")
      (value "PINS_11P_VALUE")
      (footprint "eagle-import:PINS_1-1P_VALUE")
      (libsource (lib "eagle-import") (part "PINS_11P_VALUE"))
    )
    (comp (ref "P186")
      (value "PINS_11P_VALUE")
      (footprint "eagle-import:PINS_1-1P_VALUE")
      (libsource (lib "eagle-import") (part "PINS_11P_VALUE"))
    )
    (comp (ref "P187")
      (value "PINS_11P_VALUE")
      (footprint "eagle-import:PINS_1-1P_VALUE")
      (libsource (lib "eagle-import") (part "PINS_11P_VALUE"))
    )
    (comp (ref "P188")
      (value "PINS_11P_VALUE")
      (footprint "eagle-import:PINS_1-1P_VALUE")
      (libsource (lib "eagle-import") (part "PINS_11P_VALUE"))
    )
    (comp (ref "P189")
      (value "PINS_11P_VALUE")
      (footprint "eagle-import:PINS_1-1P_VALUE")
      (libsource (lib "eagle-import") (part "PINS_11P_VALUE"))
    )
    (comp (ref "P190")
      (value "PINS_11P_VALUE")
      (footprint "eagle-import:PINS_1-1P_VALUE")
      (libsource (lib "eagle-import") (part "PINS_11P_VALUE"))
    )
    (comp (ref "P191")
      (value "PINS_11P_VALUE")
      (footprint "eagle-import:PINS_1-1P_VALUE")
      (libsource (lib "eagle-import") (part "PINS_11P_VALUE"))
    )
    (comp (ref "P192")
      (value "PINS_11P_VALUE")
      (footprint "eagle-import:PINS_1-1P_VALUE")
      (libsource (lib "eagle-import") (part "PINS_11P_VALUE"))
    )
    (comp (ref "P193")
      (value "PINS_11P_VALUE")
      (footprint "eagle-import:PINS_1-1P_VALUE")
      (libsource (lib "eagle-import") (part "PINS_11P_VALUE"))
    )
    (comp (ref "P194")
      (value "PINS_11P_VALUE")
      (footprint "eagle-import:PINS_1-1P_VALUE")
      (libsource (lib "eagle-import") (part "PINS_11P_VALUE"))
    )
    (comp (ref "P195")
      (value "PINS_11P_VALUE")
      (footprint "eagle-import:PINS_1-1P_VALUE")
      (libsource (lib "eagle-import") (part "PINS_11P_VALUE"))
    )
    (comp (ref "P196")
      (value "PINS_11P_VALUE")
      (footprint "eagle-import:PINS_1-1P_VALUE")
      (libsource (lib "eagle-import") (part "PINS_11P_VALUE"))
    )
    (comp (ref "P197")
      (value "PINS_11P_VALUE")
      (footprint "eagle-import:PINS_1-1P_VALUE")
      (libsource (lib "eagle-import") (part "PINS_11P_VALUE"))
    )
    (comp (ref "P198")
      (value "PINS_11P_VALUE")
      (footprint "eagle-import:PINS_1-1P_VALUE")
      (libsource (lib "eagle-import") (part "PINS_11P_VALUE"))
    )
    (comp (ref "P199")
      (value "PINS_11P_VALUE")
      (footprint "eagle-import:PINS_1-1P_VALUE")
      (libsource (lib "eagle-import") (part "PINS_11P_VALUE"))
    )
    (comp (ref "P200")
      (value "PINS_11P_VALUE")
      (footprint "eagle-import:PINS_1-1P_VALUE")
      (libsource (lib "eagle-import") (part "PINS_11P_VALUE"))
    )
    (comp (ref "P201")
      (value "PINS_11P_VALUE")
      (footprint "eagle-import:PINS_1-1P_VALUE")
      (libsource (lib "eagle-import") (part "PINS_11P_VALUE"))
    )
    (comp (ref "P202")
      (value "PINS_11P_VALUE")
      (footprint "eagle-import:PINS_1-1P_VALUE")
      (libsource (lib "eagle-import") (part "PINS_11P_VALUE"))
    )
    (comp (ref "P203")
      (value "PINS_11P_VALUE")
      (footprint "eagle-import:PINS_1-1P_VALUE")
      (libsource (lib "eagle-import") (part "PINS_11P_VALUE"))
    )
    (comp (ref "P204")
      (value "PINS_11P_VALUE")
      (footprint "eagle-import:PINS_1-1P_VALUE")
      (libsource (lib "eagle-import") (part "PINS_11P_VALUE"))
    )
    (comp (ref "P205")
      (value "PINS_11P_VALUE")
      (footprint "eagle-import:PINS_1-1P_VALUE")
      (libsource (lib "eagle-import") (part "PINS_11P_VALUE"))
    )
    (comp (ref "P206")
      (value "PINS_11P_VALUE")
      (footprint "eagle-import:PINS_1-1P_VALUE")
      (libsource (lib "eagle-import") (part "PINS_11P_VALUE"))
    )
    (comp (ref "P207")
      (value "PINS_11P_VALUE")
      (footprint "eagle-import:PINS_1-1P_VALUE")
      (libsource (lib "eagle-import") (part "PINS_11P_VALUE"))
    )
    (comp (ref "P208")
      (value "PINS_11P_VALUE")
      (footprint "eagle-import:PINS_1-1P_VALUE")
      (libsource (lib "eagle-import") (part "PINS_11P_VALUE"))
    )
    (comp (ref "P209")
      (value "PINS_11P_VALUE")
      (footprint "eagle-import:PINS_1-1P_VALUE")
      (libsource (lib "eagle-import") (part "PINS_11P_VALUE"))
    )
    (comp (ref "P210")
      (value "PINS_11P_VALUE")
      (footprint "eagle-import:PINS_1-1P_VALUE")
      (libsource (lib "eagle-import") (part "PINS_11P_VALUE"))
    )
    (comp (ref "P211")
      (value "PINS_11P_VALUE")
      (footprint "eagle-import:PINS_1-1P_VALUE")
      (libsource (lib "eagle-import") (part "PINS_11P_VALUE"))
    )
    (comp (ref "P212")
      (value "PINS_11P_VALUE")
      (footprint "eagle-import:PINS_1-1P_VALUE")
      (libsource (lib "eagle-import") (part "PINS_11P_VALUE"))
    )
    (comp (ref "P213")
      (value "PINS_11P_VALUE")
      (footprint "eagle-import:PINS_1-1P_VALUE")
      (libsource (lib "eagle-import") (part "PINS_11P_VALUE"))
    )
    (comp (ref "P214")
      (value "PINS_11P_VALUE")
      (footprint "eagle-import:PINS_1-1P_VALUE")
      (libsource (lib "eagle-import") (part "PINS_11P_VALUE"))
    )
    (comp (ref "P215")
      (value "PINS_11P_VALUE")
      (footprint "eagle-import:PINS_1-1P_VALUE")
      (libsource (lib "eagle-import") (part "PINS_11P_VALUE"))
    )
    (comp (ref "P216")
      (value "PINS_11P_VALUE")
      (footprint "eagle-import:PINS_1-1P_VALUE")
      (libsource (lib "eagle-import") (part "PINS_11P_VALUE"))
    )
    (comp (ref "P217")
      (value "PINS_11P_VALUE")
      (footprint "eagle-import:PINS_1-1P_VALUE")
      (libsource (lib "eagle-import") (part "PINS_11P_VALUE"))
    )
    (comp (ref "P218")
      (value "PINS_11P_VALUE")
      (footprint "eagle-import:PINS_1-1P_VALUE")
      (libsource (lib "eagle-import") (part "PINS_11P_VALUE"))
    )
    (comp (ref "P219")
      (value "PINS_11P_VALUE")
      (footprint "eagle-import:PINS_1-1P_VALUE")
      (libsource (lib "eagle-import") (part "PINS_11P_VALUE"))
    )
    (comp (ref "P220")
      (value "PINS_11P_VALUE")
      (footprint "eagle-import:PINS_1-1P_VALUE")
      (libsource (lib "eagle-import") (part "PINS_11P_VALUE"))
    )
    (comp (ref "P221")
      (value "PINS_11P_VALUE")
      (footprint "eagle-import:PINS_1-1P_VALUE")
      (libsource (lib "eagle-import") (part "PINS_11P_VALUE"))
    )
    (comp (ref "P222")
      (value "PINS_11P_VALUE")
      (footprint "eagle-import:PINS_1-1P_VALUE")
      (libsource (lib "eagle-import") (part "PINS_11P_VALUE"))
    )
    (comp (ref "P223")
      (value "PINS_11P_VALUE")
      (footprint "eagle-import:PINS_1-1P_VALUE")
      (libsource (lib "eagle-import") (part "PINS_11P_VALUE"))
    )
    (comp (ref "P224")
      (value "PINS_11P_VALUE")
      (footprint "eagle-import:PINS_1-1P_VALUE")
      (libsource (lib "eagle-import") (part "PINS_11P_VALUE"))
    )
    (comp (ref "P225")
      (value "PINS_11P_VALUE")
      (footprint "eagle-import:PINS_1-1P_VALUE")
      (libsource (lib "eagle-import") (part "PINS_11P_VALUE"))
    )
    (comp (ref "P226")
      (value "PINS_11P_VALUE")
      (footprint "eagle-import:PINS_1-1P_VALUE")
      (libsource (lib "eagle-import") (part "PINS_11P_VALUE"))
    )
    (comp (ref "P227")
      (value "PINS_11P_VALUE")
      (footprint "eagle-import:PINS_1-1P_VALUE")
      (libsource (lib "eagle-import") (part "PINS_11P_VALUE"))
    )
    (comp (ref "P228")
      (value "PINS_11P_VALUE")
      (footprint "eagle-import:PINS_1-1P_VALUE")
      (libsource (lib "eagle-import") (part "PINS_11P_VALUE"))
    )
    (comp (ref "P229")
      (value "PINS_11P_VALUE")
      (footprint "eagle-import:PINS_1-1P_VALUE")
      (libsource (lib "eagle-import") (part "PINS_11P_VALUE"))
    )
    (comp (ref "P230")
      (value "PINS_11P_VALUE")
      (footprint "eagle-import:PINS_1-1P_VALUE")
      (libsource (lib "eagle-import") (part "PINS_11P_VALUE"))
    )
    (comp (ref "P231")
      (value "PINS_11P_VALUE")
      (footprint "eagle-import:PINS_1-1P_VALUE")
      (libsource (lib "eagle-import") (part "PINS_11P_VALUE"))
    )
    (comp (ref "P232")
      (value "PINS_11P_VALUE")
      (footprint "eagle-import:PINS_1-1P_VALUE")
      (libsource (lib "eagle-import") (part "PINS_11P_VALUE"))
    )
    (comp (ref "P233")
      (value "PINS_11P_VALUE")
      (footprint "eagle-import:PINS_1-1P_VALUE")
      (libsource (lib "eagle-import") (part "PINS_11P_VALUE"))
    )
    (comp (ref "P234")
      (value "PINS_11P_VALUE")
      (footprint "eagle-import:PINS_1-1P_VALUE")
      (libsource (lib "eagle-import") (part "PINS_11P_VALUE"))
    )
    (comp (ref "P235")
      (value "PINS_11P_VALUE")
      (footprint "eagle-import:PINS_1-1P_VALUE")
      (libsource (lib "eagle-import") (part "PINS_11P_VALUE"))
    )
    (comp (ref "P236")
      (value "PINS_11P_VALUE")
      (footprint "eagle-import:PINS_1-1P_VALUE")
      (libsource (lib "eagle-import") (part "PINS_11P_VALUE"))
    )
    (comp (ref "P237")
      (value "PINS_11P_VALUE")
      (footprint "eagle-import:PINS_1-1P_VALUE")
      (libsource (lib "eagle-import") (part "PINS_11P_VALUE"))
    )
    (comp (ref "P238")
      (value "PINS_11P_VALUE")
      (footprint "eagle-import:PINS_1-1P_VALUE")
      (libsource (lib "eagle-import") (part "PINS_11P_VALUE"))
    )
    (comp (ref "P239")
      (value "PINS_11P_VALUE")
      (footprint "eagle-import:PINS_1-1P_VALUE")
      (libsource (lib "eagle-import") (part "PINS_11P_VALUE"))
    )
    (comp (ref "P240")
      (value "PINS_11P_VALUE")
      (footprint "eagle-import:PINS_1-1P_VALUE")
      (libsource (lib "eagle-import") (part "PINS_11P_VALUE"))
    )
    (comp (ref "P241")
      (value "PINS_11P_VALUE")
      (footprint "eagle-import:PINS_1-1P_VALUE")
      (libsource (lib "eagle-import") (part "PINS_11P_VALUE"))
    )
    (comp (ref "P242")
      (value "PINS_11P_VALUE")
      (footprint "eagle-import:PINS_1-1P_VALUE")
      (libsource (lib "eagle-import") (part "PINS_11P_VALUE"))
    )
    (comp (ref "P243")
      (value "PINS_11P_VALUE")
      (footprint "eagle-import:PINS_1-1P_VALUE")
      (libsource (lib "eagle-import") (part "PINS_11P_VALUE"))
    )
    (comp (ref "P244")
      (value "PINS_11P_VALUE")
      (footprint "eagle-import:PINS_1-1P_VALUE")
      (libsource (lib "eagle-import") (part "PINS_11P_VALUE"))
    )
    (comp (ref "P245")
      (value "PINS_11P_VALUE")
      (footprint "eagle-import:PINS_1-1P_VALUE")
      (libsource (lib "eagle-import") (part "PINS_11P_VALUE"))
    )
    (comp (ref "P246")
      (value "PINS_11P_VALUE")
      (footprint "eagle-import:PINS_1-1P_VALUE")
      (libsource (lib "eagle-import") (part "PINS_11P_VALUE"))
    )
    (comp (ref "P247")
      (value "PINS_11P_VALUE")
      (footprint "eagle-import:PINS_1-1P_VALUE")
      (libsource (lib "eagle-import") (part "PINS_11P_VALUE"))
    )
    (comp (ref "P248")
      (value "PINS_11P_VALUE")
      (footprint "eagle-import:PINS_1-1P_VALUE")
      (libsource (lib "eagle-import") (part "PINS_11P_VALUE"))
    )
    (comp (ref "P249")
      (value "PINS_11P_VALUE")
      (footprint "eagle-import:PINS_1-1P_VALUE")
      (libsource (lib "eagle-import") (part "PINS_11P_VALUE"))
    )
    (comp (ref "P250")
      (value "PINS_11P_VALUE")
      (footprint "eagle-import:PINS_1-1P_VALUE")
      (libsource (lib "eagle-import") (part "PINS_11P_VALUE"))
    )
    (comp (ref "P251")
      (value "PINS_11P_VALUE")
      (footprint "eagle-import:PINS_1-1P_VALUE")
      (libsource (lib "eagle-import") (part "PINS_11P_VALUE"))
    )
    (comp (ref "P252")
      (value "PINS_11P_VALUE")
      (footprint "eagle-import:PINS_1-1P_VALUE")
      (libsource (lib "eagle-import") (part "PINS_11P_VALUE"))
    )
    (comp (ref "P253")
      (value "PINS_11P_VALUE")
      (footprint "eagle-import:PINS_1-1P_VALUE")
      (libsource (lib "eagle-import") (part "PINS_11P_VALUE"))
    )
    (comp (ref "P254")
      (value "PINS_11P_VALUE")
      (footprint "eagle-import:PINS_1-1P_VALUE")
      (libsource (lib "eagle-import") (part "PINS_11P_VALUE"))
    )
    (comp (ref "P255")
      (value "PINS_11P_VALUE")
      (footprint "eagle-import:PINS_1-1P_VALUE")
      (libsource (lib "eagle-import") (part "PINS_11P_VALUE"))
    )
    (comp (ref "P256")
      (value "PINS_11P_VALUE")
      (footprint "eagle-import:PINS_1-1P_VALUE")
      (libsource (lib "eagle-import") (part "PINS_11P_VALUE"))
    )
    (comp (ref "P257")
      (value "PINS_11P_VALUE")
      (footprint "eagle-import:PINS_1-1P_VALUE")
      (libsource (lib "eagle-import") (part "PINS_11P_VALUE"))
    )
    (comp (ref "P258")
      (value "PINS_11P_VALUE")
      (footprint "eagle-import:PINS_1-1P_VALUE")
      (libsource (lib "eagle-import") (part "PINS_11P_VALUE"))
    )
    (comp (ref "P259")
      (value "PINS_11P_VALUE")
      (footprint "eagle-import:PINS_1-1P_VALUE")
      (libsource (lib "eagle-import") (part "PINS_11P_VALUE"))
    )
    (comp (ref "P260")
      (value "PINS_11P_VALUE")
      (footprint "eagle-import:PINS_1-1P_VALUE")
      (libsource (lib "eagle-import") (part "PINS_11P_VALUE"))
    )
    (comp (ref "P261")
      (value "PINS_11P_VALUE")
      (footprint "eagle-import:PINS_1-1P_VALUE")
      (libsource (lib "eagle-import") (part "PINS_11P_VALUE"))
    )
    (comp (ref "P262")
      (value "PINS_11P_VALUE")
      (footprint "eagle-import:PINS_1-1P_VALUE")
      (libsource (lib "eagle-import") (part "PINS_11P_VALUE"))
    )
    (comp (ref "P263")
      (value "PINS_11P_VALUE")
      (footprint "eagle-import:PINS_1-1P_VALUE")
      (libsource (lib "eagle-import") (part "PINS_11P_VALUE"))
    )
    (comp (ref "P264")
      (value "PINS_11P_VALUE")
      (footprint "eagle-import:PINS_1-1P_VALUE")
      (libsource (lib "eagle-import") (part "PINS_11P_VALUE"))
    )
    (comp (ref "P265")
      (value "PINS_11P_VALUE")
      (footprint "eagle-import:PINS_1-1P_VALUE")
      (libsource (lib "eagle-import") (part "PINS_11P_VALUE"))
    )
    (comp (ref "P266")
      (value "PINS_11P_VALUE")
      (footprint "eagle-import:PINS_1-1P_VALUE")
      (libsource (lib "eagle-import") (part "PINS_11P_VALUE"))
    )
    (comp (ref "P267")
      (value "PINS_11P_VALUE")
      (footprint "eagle-import:PINS_1-1P_VALUE")
      (libsource (lib "eagle-import") (part "PINS_11P_VALUE"))
    )
    (comp (ref "P268")
      (value "PINS_11P_VALUE")
      (footprint "eagle-import:PINS_1-1P_VALUE")
      (libsource (lib "eagle-import") (part "PINS_11P_VALUE"))
    )
    (comp (ref "P269")
      (value "PINS_11P_VALUE")
      (footprint "eagle-import:PINS_1-1P_VALUE")
      (libsource (lib "eagle-import") (part "PINS_11P_VALUE"))
    )
    (comp (ref "P270")
      (value "PINS_11P_VALUE")
      (footprint "eagle-import:PINS_1-1P_VALUE")
      (libsource (lib "eagle-import") (part "PINS_11P_VALUE"))
    )
    (comp (ref "P271")
      (value "PINS_11P_VALUE")
      (footprint "eagle-import:PINS_1-1P_VALUE")
      (libsource (lib "eagle-import") (part "PINS_11P_VALUE"))
    )
    (comp (ref "P272")
      (value "PINS_11P_VALUE")
      (footprint "eagle-import:PINS_1-1P_VALUE")
      (libsource (lib "eagle-import") (part "PINS_11P_VALUE"))
    )
    (comp (ref "P273")
      (value "PINS_11P_VALUE")
      (footprint "eagle-import:PINS_1-1P_VALUE")
      (libsource (lib "eagle-import") (part "PINS_11P_VALUE"))
    )
    (comp (ref "P274")
      (value "PINS_11P_VALUE")
      (footprint "eagle-import:PINS_1-1P_VALUE")
      (libsource (lib "eagle-import") (part "PINS_11P_VALUE"))
    )
    (comp (ref "P275")
      (value "PINS_11P_VALUE")
      (footprint "eagle-import:PINS_1-1P_VALUE")
      (libsource (lib "eagle-import") (part "PINS_11P_VALUE"))
    )
    (comp (ref "P276")
      (value "PINS_11P_VALUE")
      (footprint "eagle-import:PINS_1-1P_VALUE")
      (libsource (lib "eagle-import") (part "PINS_11P_VALUE"))
    )
    (comp (ref "P277")
      (value "PINS_11P_VALUE")
      (footprint "eagle-import:PINS_1-1P_VALUE")
      (libsource (lib "eagle-import") (part "PINS_11P_VALUE"))
    )
    (comp (ref "P278")
      (value "PINS_11P_VALUE")
      (footprint "eagle-import:PINS_1-1P_VALUE")
      (libsource (lib "eagle-import") (part "PINS_11P_VALUE"))
    )
    (comp (ref "P279")
      (value "PINS_11P_VALUE")
      (footprint "eagle-import:PINS_1-1P_VALUE")
      (libsource (lib "eagle-import") (part "PINS_11P_VALUE"))
    )
    (comp (ref "P280")
      (value "PINS_11P_VALUE")
      (footprint "eagle-import:PINS_1-1P_VALUE")
      (libsource (lib "eagle-import") (part "PINS_11P_VALUE"))
    )
    (comp (ref "P281")
      (value "PINS_11P_VALUE")
      (footprint "eagle-import:PINS_1-1P_VALUE")
      (libsource (lib "eagle-import") (part "PINS_11P_VALUE"))
    )
    (comp (ref "P282")
      (value "PINS_11P_VALUE")
      (footprint "eagle-import:PINS_1-1P_VALUE")
      (libsource (lib "eagle-import") (part "PINS_11P_VALUE"))
    )
    (comp (ref "P283")
      (value "PINS_11P_VALUE")
      (footprint "eagle-import:PINS_1-1P_VALUE")
      (libsource (lib "eagle-import") (part "PINS_11P_VALUE"))
    )
    (comp (ref "P284")
      (value "PINS_11P_VALUE")
      (footprint "eagle-import:PINS_1-1P_VALUE")
      (libsource (lib "eagle-import") (part "PINS_11P_VALUE"))
    )
    (comp (ref "P285")
      (value "PINS_11P_VALUE")
      (footprint "eagle-import:PINS_1-1P_VALUE")
      (libsource (lib "eagle-import") (part "PINS_11P_VALUE"))
    )
    (comp (ref "P286")
      (value "PINS_11P_VALUE")
      (footprint "eagle-import:PINS_1-1P_VALUE")
      (libsource (lib "eagle-import") (part "PINS_11P_VALUE"))
    )
    (comp (ref "P287")
      (value "PINS_11P_VALUE")
      (footprint "eagle-import:PINS_1-1P_VALUE")
      (libsource (lib "eagle-import") (part "PINS_11P_VALUE"))
    )
    (comp (ref "P288")
      (value "PINS_11P_VALUE")
      (footprint "eagle-import:PINS_1-1P_VALUE")
      (libsource (lib "eagle-import") (part "PINS_11P_VALUE"))
    )
    (comp (ref "P289")
      (value "PINS_11P_VALUE")
      (footprint "eagle-import:PINS_1-1P_VALUE")
      (libsource (lib "eagle-import") (part "PINS_11P_VALUE"))
    )
    (comp (ref "P290")
      (value "PINS_11P_VALUE")
      (footprint "eagle-import:PINS_1-1P_VALUE")
      (libsource (lib "eagle-import") (part "PINS_11P_VALUE"))
    )
    (comp (ref "P291")
      (value "PINS_11P_VALUE")
      (footprint "eagle-import:PINS_1-1P_VALUE")
      (libsource (lib "eagle-import") (part "PINS_11P_VALUE"))
    )
    (comp (ref "P292")
      (value "PINS_11P_VALUE")
      (footprint "eagle-import:PINS_1-1P_VALUE")
      (libsource (lib "eagle-import") (part "PINS_11P_VALUE"))
    )
    (comp (ref "P293")
      (value "PINS_11P_VALUE")
      (footprint "eagle-import:PINS_1-1P_VALUE")
      (libsource (lib "eagle-import") (part "PINS_11P_VALUE"))
    )
    (comp (ref "P294")
      (value "PINS_11P_VALUE")
      (footprint "eagle-import:PINS_1-1P_VALUE")
      (libsource (lib "eagle-import") (part "PINS_11P_VALUE"))
    )
    (comp (ref "P295")
      (value "PINS_11P_VALUE")
      (footprint "eagle-import:PINS_1-1P_VALUE")
      (libsource (lib "eagle-import") (part "PINS_11P_VALUE"))
    )
    (comp (ref "P296")
      (value "PINS_11P_VALUE")
      (footprint "eagle-import:PINS_1-1P_VALUE")
      (libsource (lib "eagle-import") (part "PINS_11P_VALUE"))
    )
    (comp (ref "P297")
      (value "PINS_11P_VALUE")
      (footprint "eagle-import:PINS_1-1P_VALUE")
      (libsource (lib "eagle-import") (part "PINS_11P_VALUE"))
    )
    (comp (ref "P298")
      (value "PINS_11P_VALUE")
      (footprint "eagle-import:PINS_1-1P_VALUE")
      (libsource (lib "eagle-import") (part "PINS_11P_VALUE"))
    )
    (comp (ref "P299")
      (value "PINS_11P_VALUE")
      (footprint "eagle-import:PINS_1-1P_VALUE")
      (libsource (lib "eagle-import") (part "PINS_11P_VALUE"))
    )
    (comp (ref "P300")
      (value "PINS_11P_VALUE")
      (footprint "eagle-import:PINS_1-1P_VALUE")
      (libsource (lib "eagle-import") (part "PINS_11P_VALUE"))
    )
    (comp (ref "P301")
      (value "PINS_11P_VALUE")
      (footprint "eagle-import:PINS_1-1P_VALUE")
      (libsource (lib "eagle-import") (part "PINS_11P_VALUE"))
    )
    (comp (ref "P302")
      (value "PINS_11P_VALUE")
      (footprint "eagle-import:PINS_1-1P_VALUE")
      (libsource (lib "eagle-import") (part "PINS_11P_VALUE"))
    )
    (comp (ref "P303")
      (value "PINS_11P_VALUE")
      (footprint "eagle-import:PINS_1-1P_VALUE")
      (libsource (lib "eagle-import") (part "PINS_11P_VALUE"))
    )
    (comp (ref "P304")
      (value "PINS_11P_VALUE")
      (footprint "eagle-import:PINS_1-1P_VALUE")
      (libsource (lib "eagle-import") (part "PINS_11P_VALUE"))
    )
    (comp (ref "P305")
      (value "PINS_11P_VALUE")
      (footprint "eagle-import:PINS_1-1P_VALUE")
      (libsource (lib "eagle-import") (part "PINS_11P_VALUE"))
    )
    (comp (ref "P306")
      (value "PINS_11P_VALUE")
      (footprint "eagle-import:PINS_1-1P_VALUE")
      (libsource (lib "eagle-import") (part "PINS_11P_VALUE"))
    )
    (comp (ref "P307")
      (value "PINS_11P_VALUE")
      (footprint "eagle-import:PINS_1-1P_VALUE")
      (libsource (lib "eagle-import") (part "PINS_11P_VALUE"))
    )
    (comp (ref "P308")
      (value "PINS_11P_VALUE")
      (footprint "eagle-import:PINS_1-1P_VALUE")
      (libsource (lib "eagle-import") (part "PINS_11P_VALUE"))
    )
    (comp (ref "P309")
      (value "PINS_11P_VALUE")
      (footprint "eagle-import:PINS_1-1P_VALUE")
      (libsource (lib "eagle-import") (part "PINS_11P_VALUE"))
    )
    (comp (ref "P310")
      (value "PINS_11P_VALUE")
      (footprint "eagle-import:PINS_1-1P_VALUE")
      (libsource (lib "eagle-import") (part "PINS_11P_VALUE"))
    )
    (comp (ref "P311")
      (value "PINS_11P_VALUE")
      (footprint "eagle-import:PINS_1-1P_VALUE")
      (libsource (lib "eagle-import") (part "PINS_11P_VALUE"))
    )
    (comp (ref "P312")
      (value "PINS_11P_VALUE")
      (footprint "eagle-import:PINS_1-1P_VALUE")
      (libsource (lib "eagle-import") (part "PINS_11P_VALUE"))
    )
    (comp (ref "P313")
      (value "PINS_11P_VALUE")
      (footprint "eagle-import:PINS_1-1P_VALUE")
      (libsource (lib "eagle-import") (part "PINS_11P_VALUE"))
    )
    (comp (ref "P314")
      (value "PINS_11P_VALUE")
      (footprint "eagle-import:PINS_1-1P_VALUE")
      (libsource (lib "eagle-import") (part "PINS_11P_VALUE"))
    )
    (comp (ref "P315")
      (value "PINS_11P_VALUE")
      (footprint "eagle-import:PINS_1-1P_VALUE")
      (libsource (lib "eagle-import") (part "PINS_11P_VALUE"))
    )
    (comp (ref "P316")
      (value "PINS_11P_VALUE")
      (footprint "eagle-import:PINS_1-1P_VALUE")
      (libsource (lib "eagle-import") (part "PINS_11P_VALUE"))
    )
    (comp (ref "P317")
      (value "PINS_11P_VALUE")
      (footprint "eagle-import:PINS_1-1P_VALUE")
      (libsource (lib "eagle-import") (part "PINS_11P_VALUE"))
    )
    (comp (ref "P318")
      (value "PINS_11P_VALUE")
      (footprint "eagle-import:PINS_1-1P_VALUE")
      (libsource (lib "eagle-import") (part "PINS_11P_VALUE"))
    )
    (comp (ref "P319")
      (value "PINS_11P_VALUE")
      (footprint "eagle-import:PINS_1-1P_VALUE")
      (libsource (lib "eagle-import") (part "PINS_11P_VALUE"))
    )
    (comp (ref "P320")
      (value "PINS_11P_VALUE")
      (footprint "eagle-import:PINS_1-1P_VALUE")
      (libsource (lib "eagle-import") (part "PINS_11P_VALUE"))
    )
    (comp (ref "P321")
      (value "PINS_11P_VALUE")
      (footprint "eagle-import:PINS_1-1P_VALUE")
      (libsource (lib "eagle-import") (part "PINS_11P_VALUE"))
    )
    (comp (ref "P322")
      (value "PINS_11P_VALUE")
      (footprint "eagle-import:PINS_1-1P_VALUE")
      (libsource (lib "eagle-import") (part "PINS_11P_VALUE"))
    )
    (comp (ref "P323")
      (value "PINS_11P_VALUE")
      (footprint "eagle-import:PINS_1-1P_VALUE")
      (libsource (lib "eagle-import") (part "PINS_11P_VALUE"))
    )
    (comp (ref "P324")
      (value "PINS_11P_VALUE")
      (footprint "eagle-import:PINS_1-1P_VALUE")
      (libsource (lib "eagle-import") (part "PINS_11P_VALUE"))
    )
    (comp (ref "P325")
      (value "PINS_11P_VALUE")
      (footprint "eagle-import:PINS_1-1P_VALUE")
      (libsource (lib "eagle-import") (part "PINS_11P_VALUE"))
    )
    (comp (ref "P326")
      (value "PINS_11P_VALUE")
      (footprint "eagle-import:PINS_1-1P_VALUE")
      (libsource (lib "eagle-import") (part "PINS_11P_VALUE"))
    )
    (comp (ref "P327")
      (value "PINS_11P_VALUE")
      (footprint "eagle-import:PINS_1-1P_VALUE")
      (libsource (lib "eagle-import") (part "PINS_11P_VALUE"))
    )
    (comp (ref "P328")
      (value "PINS_11P_VALUE")
      (footprint "eagle-import:PINS_1-1P_VALUE")
      (libsource (lib "eagle-import") (part "PINS_11P_VALUE"))
    )
    (comp (ref "P329")
      (value "PINS_11P_VALUE")
      (footprint "eagle-import:PINS_1-1P_VALUE")
      (libsource (lib "eagle-import") (part "PINS_11P_VALUE"))
    )
    (comp (ref "P330")
      (value "PINS_11P_VALUE")
      (footprint "eagle-import:PINS_1-1P_VALUE")
      (libsource (lib "eagle-import") (part "PINS_11P_VALUE"))
    )
    (comp (ref "P331")
      (value "PINS_11P_VALUE")
      (footprint "eagle-import:PINS_1-1P_VALUE")
      (libsource (lib "eagle-import") (part "PINS_11P_VALUE"))
    )
    (comp (ref "P332")
      (value "PINS_11P_VALUE")
      (footprint "eagle-import:PINS_1-1P_VALUE")
      (libsource (lib "eagle-import") (part "PINS_11P_VALUE"))
    )
    (comp (ref "P333")
      (value "PINS_11P_VALUE")
      (footprint "eagle-import:PINS_1-1P_VALUE")
      (libsource (lib "eagle-import") (part "PINS_11P_VALUE"))
    )
    (comp (ref "P334")
      (value "PINS_11P_VALUE")
      (footprint "eagle-import:PINS_1-1P_VALUE")
      (libsource (lib "eagle-import") (part "PINS_11P_VALUE"))
    )
    (comp (ref "P335")
      (value "PINS_11P_VALUE")
      (footprint "eagle-import:PINS_1-1P_VALUE")
      (libsource (lib "eagle-import") (part "PINS_11P_VALUE"))
    )
    (comp (ref "P336")
      (value "PINS_11P_VALUE")
      (footprint "eagle-import:PINS_1-1P_VALUE")
      (libsource (lib "eagle-import") (part "PINS_11P_VALUE"))
    )
    (comp (ref "P337")
      (value "PINS_11P_VALUE")
      (footprint "eagle-import:PINS_1-1P_VALUE")
      (libsource (lib "eagle-import") (part "PINS_11P_VALUE"))
    )
    (comp (ref "P338")
      (value "PINS_11P_VALUE")
      (footprint "eagle-import:PINS_1-1P_VALUE")
      (libsource (lib "eagle-import") (part "PINS_11P_VALUE"))
    )
    (comp (ref "P339")
      (value "PINS_11P_VALUE")
      (footprint "eagle-import:PINS_1-1P_VALUE")
      (libsource (lib "eagle-import") (part "PINS_11P_VALUE"))
    )
    (comp (ref "P340")
      (value "PINS_11P_VALUE")
      (footprint "eagle-import:PINS_1-1P_VALUE")
      (libsource (lib "eagle-import") (part "PINS_11P_VALUE"))
    )
    (comp (ref "FRDM1")
      (value "FRDM-KL25ZNORMAL")
      (footprint "eagle-import:FRDM_KL25Z_NORMAL")
      (fields (field (name "MF") "NXP USA") (field (name "MP") "FRDM-KL25Z"))
      (libsource (lib "eagle-import") (part "FRDM-KL25ZNORMAL"))
    )
    (comp (ref "P57")
      (value "3V3")
      (footprint "eagle-import:PINS_1-3P_VALUE")
      (libsource (lib "eagle-import") (part "PINS_13P_VALUE"))
    )
    (comp (ref "P58")
      (value "5V")
      (footprint "eagle-import:PINS_1-3P_VALUE")
      (libsource (lib "eagle-import") (part "PINS_13P_VALUE"))
    )
    (comp (ref "P59")
      (value "VIN")
      (footprint "eagle-import:PINS_1-3P_VALUE")
      (libsource (lib "eagle-import") (part "PINS_13P_VALUE"))
    )
    (comp (ref "P102")
      (value "GND")
      (footprint "eagle-import:PINS_1-3P_VALUE")
      (libsource (lib "eagle-import") (part "PINS_13P_VALUE"))
    )
    (comp (ref "P103")
      (value "GND")
      (footprint "eagle-import:PINS_1-3P_VALUE")
      (libsource (lib "eagle-import") (part "PINS_13P_VALUE"))
    )
    (comp (ref "P114")
      (value "GND")
      (footprint "eagle-import:PINS_1-3P_VALUE")
      (libsource (lib "eagle-import") (part "PINS_13P_VALUE"))
    )
    (comp (ref "U$1")
      (value "MINIPCB_LOGO")
      (footprint "eagle-import:MINIPCB-LOGO")
      (libsource (lib "eagle-import") (part "MINIPCB_LOGO"))
    )
  )
  (nets
    (net (code "1") (name "GND") (class "Default")
      (node (ref "FRDM1") (pin "GND0") (pinfunction "GND0_GND0") (pintype "bidirectional"))
      (node (ref "FRDM1") (pin "GND1") (pinfunction "GND1_GND1") (pintype "bidirectional"))
      (node (ref "FRDM1") (pin "GND2") (pinfunction "GND2_GND2") (pintype "bidirectional"))
      (node (ref "P102") (pin "1") (pinfunction "1_1") (pintype "bidirectional"))
      (node (ref "P102") (pin "2") (pinfunction "1_2") (pintype "bidirectional"))
      (node (ref "P102") (pin "3") (pinfunction "1_3") (pintype "bidirectional"))
      (node (ref "P103") (pin "1") (pinfunction "1_1") (pintype "bidirectional"))
      (node (ref "P103") (pin "2") (pinfunction "1_2") (pintype "bidirectional"))
      (node (ref "P103") (pin "3") (pinfunction "1_3") (pintype "bidirectional"))
      (node (ref "P114") (pin "1") (pinfunction "1_1") (pintype "bidirectional"))
      (node (ref "P114") (pin "2") (pinfunction "1_2") (pintype "bidirectional"))
      (node (ref "P114") (pin "3") (pinfunction "1_3") (pintype "bidirectional"))
    )
    (net (code "2") (name "Net-(FRDM1-3V3)") (class "Default")
      (node (ref "FRDM1") (pin "P3V3") (pinfunction "3V3_P3V3") (pintype "bidirectional"))
      (node (ref "P57") (pin "1") (pinfunction "1_1") (pintype "bidirectional"))
      (node (ref "P57") (pin "2") (pinfunction "1_2") (pintype "bidirectional"))
      (node (ref "P57") (pin "3") (pinfunction "1_3") (pintype "bidirectional"))
    )
    (net (code "3") (name "Net-(FRDM1-Pad5V)") (class "Default")
      (node (ref "FRDM1") (pin "5V") (pinfunction "5V_5V") (pintype "bidirectional"))
      (node (ref "P58") (pin "1") (pinfunction "1_1") (pintype "bidirectional"))
      (node (ref "P58") (pin "2") (pinfunction "1_2") (pintype "bidirectional"))
      (node (ref "P58") (pin "3") (pinfunction "1_3") (pintype "bidirectional"))
    )
    (net (code "4") (name "Net-(FRDM1-PadVIN)") (class "Default")
      (node (ref "FRDM1") (pin "VIN") (pinfunction "VIN_VIN") (pintype "bidirectional"))
      (node (ref "P59") (pin "1") (pinfunction "1_1") (pintype "bidirectional"))
      (node (ref "P59") (pin "2") (pinfunction "1_2") (pintype "bidirectional"))
      (node (ref "P59") (pin "3") (pinfunction "1_3") (pintype "bidirectional"))
    )
    (net (code "5") (name "unconnected-(FRDM1-A0{slash}PTB0-PadA0)") (class "Default")
      (node (ref "FRDM1") (pin "A0") (pinfunction "A0/PTB0_A0") (pintype "bidirectional"))
    )
    (net (code "6") (name "unconnected-(FRDM1-A1{slash}PTB1-PadA1)") (class "Default")
      (node (ref "FRDM1") (pin "A1") (pinfunction "A1/PTB1_A1") (pintype "bidirectional"))
    )
    (net (code "7") (name "unconnected-(FRDM1-A2{slash}PTB2-PadA2)") (class "Default")
      (node (ref "FRDM1") (pin "A2") (pinfunction "A2/PTB2_A2") (pintype "bidirectional"))
    )
    (net (code "8") (name "unconnected-(FRDM1-A3{slash}PTB3-PadA3)") (class "Default")
      (node (ref "FRDM1") (pin "A3") (pinfunction "A3/PTB3_A3") (pintype "bidirectional"))
    )
    (net (code "9") (name "unconnected-(FRDM1-A4{slash}PTC2-PadA4)") (class "Default")
      (node (ref "FRDM1") (pin "A4") (pinfunction "A4/PTC2_A4") (pintype "bidirectional"))
    )
    (net (code "10") (name "unconnected-(FRDM1-A5{slash}PTC1-PadA5)") (class "Default")
      (node (ref "FRDM1") (pin "A5") (pinfunction "A5/PTC1_A5") (pintype "bidirectional"))
    )
    (net (code "11") (name "unconnected-(FRDM1-D0{slash}PTA1-PadD0)") (class "Default")
      (node (ref "FRDM1") (pin "D0") (pinfunction "D0/PTA1_D0") (pintype "bidirectional"))
    )
    (net (code "12") (name "unconnected-(FRDM1-D1{slash}PTA2-PadD1)") (class "Default")
      (node (ref "FRDM1") (pin "D1") (pinfunction "D1/PTA2_D1") (pintype "bidirectional"))
    )
    (net (code "13") (name "unconnected-(FRDM1-D2{slash}PTD4-PadD2)") (class "Default")
      (node (ref "FRDM1") (pin "D2") (pinfunction "D2/PTD4_D2") (pintype "bidirectional"))
    )
    (net (code "14") (name "unconnected-(FRDM1-D3{slash}PTA12-PadD3)") (class "Default")
      (node (ref "FRDM1") (pin "D3") (pinfunction "D3/PTA12_D3") (pintype "bidirectional"))
    )
    (net (code "15") (name "unconnected-(FRDM1-D4{slash}PTA4-PadD4)") (class "Default")
      (node (ref "FRDM1") (pin "D4") (pinfunction "D4/PTA4_D4") (pintype "bidirectional"))
    )
    (net (code "16") (name "unconnected-(FRDM1-D5{slash}PTA5-PadD5)") (class "Default")
      (node (ref "FRDM1") (pin "D5") (pinfunction "D5/PTA5_D5") (pintype "bidirectional"))
    )
    (net (code "17") (name "unconnected-(FRDM1-D6{slash}PTC8-PadD6)") (class "Default")
      (node (ref "FRDM1") (pin "D6") (pinfunction "D6/PTC8_D6") (pintype "bidirectional"))
    )
    (net (code "18") (name "unconnected-(FRDM1-D7{slash}PTC9-PadD7)") (class "Default")
      (node (ref "FRDM1") (pin "D7") (pinfunction "D7/PTC9_D7") (pintype "bidirectional"))
    )
    (net (code "19") (name "unconnected-(FRDM1-D8{slash}PTA13-PadD8)") (class "Default")
      (node (ref "FRDM1") (pin "D8") (pinfunction "D8/PTA13_D8") (pintype "bidirectional"))
    )
    (net (code "20") (name "unconnected-(FRDM1-D9{slash}PTD5-PadD9)") (class "Default")
      (node (ref "FRDM1") (pin "D9") (pinfunction "D9/PTD5_D9") (pintype "bidirectional"))
    )
    (net (code "21") (name "unconnected-(FRDM1-D10{slash}PTD0-PadD10)") (class "Default")
      (node (ref "FRDM1") (pin "D10") (pinfunction "D10/PTD0_D10") (pintype "bidirectional"))
    )
    (net (code "22") (name "unconnected-(FRDM1-D11{slash}PTD2-PadD11)") (class "Default")
      (node (ref "FRDM1") (pin "D11") (pinfunction "D11/PTD2_D11") (pintype "bidirectional"))
    )
    (net (code "23") (name "unconnected-(FRDM1-D12{slash}PTD3-PadD12)") (class "Default")
      (node (ref "FRDM1") (pin "D12") (pinfunction "D12/PTD3_D12") (pintype "bidirectional"))
    )
    (net (code "24") (name "unconnected-(FRDM1-D13{slash}PTD1-PadD13)") (class "Default")
      (node (ref "FRDM1") (pin "D13") (pinfunction "D13/PTD1_D13") (pintype "bidirectional"))
    )
    (net (code "25") (name "unconnected-(FRDM1-IOREF{slash}3V3-Pad3V3)") (class "Default")
      (node (ref "FRDM1") (pin "3V3") (pinfunction "IOREF/3V3_3V3") (pintype "bidirectional"))
    )
    (net (code "26") (name "unconnected-(FRDM1-NC-PadNC2)") (class "Default")
      (node (ref "FRDM1") (pin "NC2") (pinfunction "NC_NC2") (pintype "bidirectional"))
    )
    (net (code "27") (name "unconnected-(FRDM1-NC{slash}SDAPTD5-PadNC1)") (class "Default")
      (node (ref "FRDM1") (pin "NC1") (pinfunction "NC/SDAPTD5_NC1") (pintype "bidirectional"))
    )
    (net (code "28") (name "unconnected-(FRDM1-PadAREF)") (class "Default")
      (node (ref "FRDM1") (pin "AREF") (pinfunction "AREF_AREF") (pintype "bidirectional"))
    )
    (net (code "29") (name "unconnected-(FRDM1-PadPTA16)") (class "Default")
      (node (ref "FRDM1") (pin "PTA16") (pinfunction "PTA16_PTA16") (pintype "bidirectional"))
    )
    (net (code "30") (name "unconnected-(FRDM1-PadPTA17)") (class "Default")
      (node (ref "FRDM1") (pin "PTA17") (pinfunction "PTA17_PTA17") (pintype "bidirectional"))
    )
    (net (code "31") (name "unconnected-(FRDM1-PadPTB8)") (class "Default")
      (node (ref "FRDM1") (pin "PTB8") (pinfunction "PTB8_PTB8") (pintype "bidirectional"))
    )
    (net (code "32") (name "unconnected-(FRDM1-PadPTB9)") (class "Default")
      (node (ref "FRDM1") (pin "PTB9") (pinfunction "PTB9_PTB9") (pintype "bidirectional"))
    )
    (net (code "33") (name "unconnected-(FRDM1-PadPTB10)") (class "Default")
      (node (ref "FRDM1") (pin "PTB10") (pinfunction "PTB10_PTB10") (pintype "bidirectional"))
    )
    (net (code "34") (name "unconnected-(FRDM1-PadPTB11)") (class "Default")
      (node (ref "FRDM1") (pin "PTB11") (pinfunction "PTB11_PTB11") (pintype "bidirectional"))
    )
    (net (code "35") (name "unconnected-(FRDM1-PadPTC0)") (class "Default")
      (node (ref "FRDM1") (pin "PTC0") (pinfunction "PTC0_PTC0") (pintype "bidirectional"))
    )
    (net (code "36") (name "unconnected-(FRDM1-PadPTC3)") (class "Default")
      (node (ref "FRDM1") (pin "PTC3") (pinfunction "PTC3_PTC3") (pintype "bidirectional"))
    )
    (net (code "37") (name "unconnected-(FRDM1-PadPTC4)") (class "Default")
      (node (ref "FRDM1") (pin "PTC4") (pinfunction "PTC4_PTC4") (pintype "bidirectional"))
    )
    (net (code "38") (name "unconnected-(FRDM1-PadPTC5)") (class "Default")
      (node (ref "FRDM1") (pin "PTC5") (pinfunction "PTC5_PTC5") (pintype "bidirectional"))
    )
    (net (code "39") (name "unconnected-(FRDM1-PadPTC6)") (class "Default")
      (node (ref "FRDM1") (pin "PTC6") (pinfunction "PTC6_PTC6") (pintype "bidirectional"))
    )
    (net (code "40") (name "unconnected-(FRDM1-PadPTC7)") (class "Default")
      (node (ref "FRDM1") (pin "PTC7") (pinfunction "PTC7_PTC7") (pintype "bidirectional"))
    )
    (net (code "41") (name "unconnected-(FRDM1-PadPTC10)") (class "Default")
      (node (ref "FRDM1") (pin "PTC10") (pinfunction "PTC10_PTC10") (pintype "bidirectional"))
    )
    (net (code "42") (name "unconnected-(FRDM1-PadPTC11)") (class "Default")
      (node (ref "FRDM1") (pin "PTC11") (pinfunction "PTC11_PTC11") (pintype "bidirectional"))
    )
    (net (code "43") (name "unconnected-(FRDM1-PadPTC12)") (class "Default")
      (node (ref "FRDM1") (pin "PTC12") (pinfunction "PTC12_PTC12") (pintype "bidirectional"))
    )
    (net (code "44") (name "unconnected-(FRDM1-PadPTC13)") (class "Default")
      (node (ref "FRDM1") (pin "PTC13") (pinfunction "PTC13_PTC13") (pintype "bidirectional"))
    )
    (net (code "45") (name "unconnected-(FRDM1-PadPTC16)") (class "Default")
      (node (ref "FRDM1") (pin "PTC16") (pinfunction "PTC16_PTC16") (pintype "bidirectional"))
    )
    (net (code "46") (name "unconnected-(FRDM1-PadPTC17)") (class "Default")
      (node (ref "FRDM1") (pin "PTC17") (pinfunction "PTC17_PTC17") (pintype "bidirectional"))
    )
    (net (code "47") (name "unconnected-(FRDM1-PadPTD6)") (class "Default")
      (node (ref "FRDM1") (pin "PTD6") (pinfunction "PTD6_PTD6") (pintype "bidirectional"))
    )
    (net (code "48") (name "unconnected-(FRDM1-PadPTD7)") (class "Default")
      (node (ref "FRDM1") (pin "PTD7") (pinfunction "PTD7_PTD7") (pintype "bidirectional"))
    )
    (net (code "49") (name "unconnected-(FRDM1-PadPTE2)") (class "Default")
      (node (ref "FRDM1") (pin "PTE2") (pinfunction "PTE2_PTE2") (pintype "bidirectional"))
    )
    (net (code "50") (name "unconnected-(FRDM1-PadPTE3)") (class "Default")
      (node (ref "FRDM1") (pin "PTE3") (pinfunction "PTE3_PTE3") (pintype "bidirectional"))
    )
    (net (code "51") (name "unconnected-(FRDM1-PadPTE4)") (class "Default")
      (node (ref "FRDM1") (pin "PTE4") (pinfunction "PTE4_PTE4") (pintype "bidirectional"))
    )
    (net (code "52") (name "unconnected-(FRDM1-PadPTE5)") (class "Default")
      (node (ref "FRDM1") (pin "PTE5") (pinfunction "PTE5_PTE5") (pintype "bidirectional"))
    )
    (net (code "53") (name "unconnected-(FRDM1-PadPTE20)") (class "Default")
      (node (ref "FRDM1") (pin "PTE20") (pinfunction "PTE20_PTE20") (pintype "bidirectional"))
    )
    (net (code "54") (name "unconnected-(FRDM1-PadPTE21)") (class "Default")
      (node (ref "FRDM1") (pin "PTE21") (pinfunction "PTE21_PTE21") (pintype "bidirectional"))
    )
    (net (code "55") (name "unconnected-(FRDM1-PadPTE22)") (class "Default")
      (node (ref "FRDM1") (pin "PTE22") (pinfunction "PTE22_PTE22") (pintype "bidirectional"))
    )
    (net (code "56") (name "unconnected-(FRDM1-PadPTE23)") (class "Default")
      (node (ref "FRDM1") (pin "PTE23") (pinfunction "PTE23_PTE23") (pintype "bidirectional"))
    )
    (net (code "57") (name "unconnected-(FRDM1-PadPTE29)") (class "Default")
      (node (ref "FRDM1") (pin "PTE29") (pinfunction "PTE29_PTE29") (pintype "bidirectional"))
    )
    (net (code "58") (name "unconnected-(FRDM1-PadPTE30)") (class "Default")
      (node (ref "FRDM1") (pin "PTE30") (pinfunction "PTE30_PTE30") (pintype "bidirectional"))
    )
    (net (code "59") (name "unconnected-(FRDM1-PadPTE31)") (class "Default")
      (node (ref "FRDM1") (pin "PTE31") (pinfunction "PTE31_PTE31") (pintype "bidirectional"))
    )
    (net (code "60") (name "unconnected-(FRDM1-RST-PadRESET)") (class "Default")
      (node (ref "FRDM1") (pin "RESET") (pinfunction "RST_RESET") (pintype "bidirectional"))
    )
    (net (code "61") (name "unconnected-(FRDM1-SCL{slash}PTE1-PadD15)") (class "Default")
      (node (ref "FRDM1") (pin "D15") (pinfunction "SCL/PTE1_D15") (pintype "bidirectional"))
    )
    (net (code "62") (name "unconnected-(FRDM1-SDA{slash}PTE0-PadD14)") (class "Default")
      (node (ref "FRDM1") (pin "D14") (pinfunction "SDA/PTE0_D14") (pintype "bidirectional"))
    )
    (net (code "63") (name "unconnected-(P1-Pad1)") (class "Default")
      (node (ref "P1") (pin "1") (pinfunction "1_1") (pintype "bidirectional"))
    )
    (net (code "64") (name "unconnected-(P2-Pad1)") (class "Default")
      (node (ref "P2") (pin "1") (pinfunction "1_1") (pintype "bidirectional"))
    )
    (net (code "65") (name "unconnected-(P3-Pad1)") (class "Default")
      (node (ref "P3") (pin "1") (pinfunction "1_1") (pintype "bidirectional"))
    )
    (net (code "66") (name "unconnected-(P4-Pad1)") (class "Default")
      (node (ref "P4") (pin "1") (pinfunction "1_1") (pintype "bidirectional"))
    )
    (net (code "67") (name "unconnected-(P5-Pad1)") (class "Default")
      (node (ref "P5") (pin "1") (pinfunction "1_1") (pintype "bidirectional"))
    )
    (net (code "68") (name "unconnected-(P6-Pad1)") (class "Default")
      (node (ref "P6") (pin "1") (pinfunction "1_1") (pintype "bidirectional"))
    )
    (net (code "69") (name "unconnected-(P7-Pad1)") (class "Default")
      (node (ref "P7") (pin "1") (pinfunction "1_1") (pintype "bidirectional"))
    )
    (net (code "70") (name "unconnected-(P8-Pad1)") (class "Default")
      (node (ref "P8") (pin "1") (pinfunction "1_1") (pintype "bidirectional"))
    )
    (net (code "71") (name "unconnected-(P9-Pad1)") (class "Default")
      (node (ref "P9") (pin "1") (pinfunction "1_1") (pintype "bidirectional"))
    )
    (net (code "72") (name "unconnected-(P10-Pad1)") (class "Default")
      (node (ref "P10") (pin "1") (pinfunction "1_1") (pintype "bidirectional"))
    )
    (net (code "73") (name "unconnected-(P11-Pad1)") (class "Default")
      (node (ref "P11") (pin "1") (pinfunction "1_1") (pintype "bidirectional"))
    )
    (net (code "74") (name "unconnected-(P12-Pad1)") (class "Default")
      (node (ref "P12") (pin "1") (pinfunction "1_1") (pintype "bidirectional"))
    )
    (net (code "75") (name "unconnected-(P13-Pad1)") (class "Default")
      (node (ref "P13") (pin "1") (pinfunction "1_1") (pintype "bidirectional"))
    )
    (net (code "76") (name "unconnected-(P14-Pad1)") (class "Default")
      (node (ref "P14") (pin "1") (pinfunction "1_1") (pintype "bidirectional"))
    )
    (net (code "77") (name "unconnected-(P15-Pad1)") (class "Default")
      (node (ref "P15") (pin "1") (pinfunction "1_1") (pintype "bidirectional"))
    )
    (net (code "78") (name "unconnected-(P16-Pad1)") (class "Default")
      (node (ref "P16") (pin "1") (pinfunction "1_1") (pintype "bidirectional"))
    )
    (net (code "79") (name "unconnected-(P17-Pad1)") (class "Default")
      (node (ref "P17") (pin "1") (pinfunction "1_1") (pintype "bidirectional"))
    )
    (net (code "80") (name "unconnected-(P18-Pad1)") (class "Default")
      (node (ref "P18") (pin "1") (pinfunction "1_1") (pintype "bidirectional"))
    )
    (net (code "81") (name "unconnected-(P19-Pad1)") (class "Default")
      (node (ref "P19") (pin "1") (pinfunction "1_1") (pintype "bidirectional"))
    )
    (net (code "82") (name "unconnected-(P20-Pad1)") (class "Default")
      (node (ref "P20") (pin "1") (pinfunction "1_1") (pintype "bidirectional"))
    )
    (net (code "83") (name "unconnected-(P21-Pad1)") (class "Default")
      (node (ref "P21") (pin "1") (pinfunction "1_1") (pintype "bidirectional"))
    )
    (net (code "84") (name "unconnected-(P22-Pad1)") (class "Default")
      (node (ref "P22") (pin "1") (pinfunction "1_1") (pintype "bidirectional"))
    )
    (net (code "85") (name "unconnected-(P23-Pad1)") (class "Default")
      (node (ref "P23") (pin "1") (pinfunction "1_1") (pintype "bidirectional"))
    )
    (net (code "86") (name "unconnected-(P24-Pad1)") (class "Default")
      (node (ref "P24") (pin "1") (pinfunction "1_1") (pintype "bidirectional"))
    )
    (net (code "87") (name "unconnected-(P25-Pad1)") (class "Default")
      (node (ref "P25") (pin "1") (pinfunction "1_1") (pintype "bidirectional"))
    )
    (net (code "88") (name "unconnected-(P26-Pad1)") (class "Default")
      (node (ref "P26") (pin "1") (pinfunction "1_1") (pintype "bidirectional"))
    )
    (net (code "89") (name "unconnected-(P27-Pad1)") (class "Default")
      (node (ref "P27") (pin "1") (pinfunction "1_1") (pintype "bidirectional"))
    )
    (net (code "90") (name "unconnected-(P28-Pad1)") (class "Default")
      (node (ref "P28") (pin "1") (pinfunction "1_1") (pintype "bidirectional"))
    )
    (net (code "91") (name "unconnected-(P29-Pad1)") (class "Default")
      (node (ref "P29") (pin "1") (pinfunction "1_1") (pintype "bidirectional"))
    )
    (net (code "92") (name "unconnected-(P30-Pad1)") (class "Default")
      (node (ref "P30") (pin "1") (pinfunction "1_1") (pintype "bidirectional"))
    )
    (net (code "93") (name "unconnected-(P31-Pad1)") (class "Default")
      (node (ref "P31") (pin "1") (pinfunction "1_1") (pintype "bidirectional"))
    )
    (net (code "94") (name "unconnected-(P32-Pad1)") (class "Default")
      (node (ref "P32") (pin "1") (pinfunction "1_1") (pintype "bidirectional"))
    )
    (net (code "95") (name "unconnected-(P33-Pad1)") (class "Default")
      (node (ref "P33") (pin "1") (pinfunction "1_1") (pintype "bidirectional"))
    )
    (net (code "96") (name "unconnected-(P34-Pad1)") (class "Default")
      (node (ref "P34") (pin "1") (pinfunction "1_1") (pintype "bidirectional"))
    )
    (net (code "97") (name "unconnected-(P35-Pad1)") (class "Default")
      (node (ref "P35") (pin "1") (pinfunction "1_1") (pintype "bidirectional"))
    )
    (net (code "98") (name "unconnected-(P36-Pad1)") (class "Default")
      (node (ref "P36") (pin "1") (pinfunction "1_1") (pintype "bidirectional"))
    )
    (net (code "99") (name "unconnected-(P37-Pad1)") (class "Default")
      (node (ref "P37") (pin "1") (pinfunction "1_1") (pintype "bidirectional"))
    )
    (net (code "100") (name "unconnected-(P38-Pad1)") (class "Default")
      (node (ref "P38") (pin "1") (pinfunction "1_1") (pintype "bidirectional"))
    )
    (net (code "101") (name "unconnected-(P39-Pad1)") (class "Default")
      (node (ref "P39") (pin "1") (pinfunction "1_1") (pintype "bidirectional"))
    )
    (net (code "102") (name "unconnected-(P40-Pad1)") (class "Default")
      (node (ref "P40") (pin "1") (pinfunction "1_1") (pintype "bidirectional"))
    )
    (net (code "103") (name "unconnected-(P41-Pad1)") (class "Default")
      (node (ref "P41") (pin "1") (pinfunction "1_1") (pintype "bidirectional"))
    )
    (net (code "104") (name "unconnected-(P42-Pad1)") (class "Default")
      (node (ref "P42") (pin "1") (pinfunction "1_1") (pintype "bidirectional"))
    )
    (net (code "105") (name "unconnected-(P43-Pad1)") (class "Default")
      (node (ref "P43") (pin "1") (pinfunction "1_1") (pintype "bidirectional"))
    )
    (net (code "106") (name "unconnected-(P44-Pad1)") (class "Default")
      (node (ref "P44") (pin "1") (pinfunction "1_1") (pintype "bidirectional"))
    )
    (net (code "107") (name "unconnected-(P45-Pad1)") (class "Default")
      (node (ref "P45") (pin "1") (pinfunction "1_1") (pintype "bidirectional"))
    )
    (net (code "108") (name "unconnected-(P46-Pad1)") (class "Default")
      (node (ref "P46") (pin "1") (pinfunction "1_1") (pintype "bidirectional"))
    )
    (net (code "109") (name "unconnected-(P47-Pad1)") (class "Default")
      (node (ref "P47") (pin "1") (pinfunction "1_1") (pintype "bidirectional"))
    )
    (net (code "110") (name "unconnected-(P48-Pad1)") (class "Default")
      (node (ref "P48") (pin "1") (pinfunction "1_1") (pintype "bidirectional"))
    )
    (net (code "111") (name "unconnected-(P49-Pad1)") (class "Default")
      (node (ref "P49") (pin "1") (pinfunction "1_1") (pintype "bidirectional"))
    )
    (net (code "112") (name "unconnected-(P50-Pad1)") (class "Default")
      (node (ref "P50") (pin "1") (pinfunction "1_1") (pintype "bidirectional"))
    )
    (net (code "113") (name "unconnected-(P51-Pad1)") (class "Default")
      (node (ref "P51") (pin "1") (pinfunction "1_1") (pintype "bidirectional"))
    )
    (net (code "114") (name "unconnected-(P52-Pad1)") (class "Default")
      (node (ref "P52") (pin "1") (pinfunction "1_1") (pintype "bidirectional"))
    )
    (net (code "115") (name "unconnected-(P53-Pad1)") (class "Default")
      (node (ref "P53") (pin "1") (pinfunction "1_1") (pintype "bidirectional"))
    )
    (net (code "116") (name "unconnected-(P54-Pad1)") (class "Default")
      (node (ref "P54") (pin "1") (pinfunction "1_1") (pintype "bidirectional"))
    )
    (net (code "117") (name "unconnected-(P55-Pad1)") (class "Default")
      (node (ref "P55") (pin "1") (pinfunction "1_1") (pintype "bidirectional"))
    )
    (net (code "118") (name "unconnected-(P56-Pad1)") (class "Default")
      (node (ref "P56") (pin "1") (pinfunction "1_1") (pintype "bidirectional"))
    )
    (net (code "119") (name "unconnected-(P60-Pad1)") (class "Default")
      (node (ref "P60") (pin "1") (pinfunction "1_1") (pintype "bidirectional"))
    )
    (net (code "120") (name "unconnected-(P61-Pad1)") (class "Default")
      (node (ref "P61") (pin "1") (pinfunction "1_1") (pintype "bidirectional"))
    )
    (net (code "121") (name "unconnected-(P62-Pad1)") (class "Default")
      (node (ref "P62") (pin "1") (pinfunction "1_1") (pintype "bidirectional"))
    )
    (net (code "122") (name "unconnected-(P63-Pad1)") (class "Default")
      (node (ref "P63") (pin "1") (pinfunction "1_1") (pintype "bidirectional"))
    )
    (net (code "123") (name "unconnected-(P64-Pad1)") (class "Default")
      (node (ref "P64") (pin "1") (pinfunction "1_1") (pintype "bidirectional"))
    )
    (net (code "124") (name "unconnected-(P65-Pad1)") (class "Default")
      (node (ref "P65") (pin "1") (pinfunction "1_1") (pintype "bidirectional"))
    )
    (net (code "125") (name "unconnected-(P66-Pad1)") (class "Default")
      (node (ref "P66") (pin "1") (pinfunction "1_1") (pintype "bidirectional"))
    )
    (net (code "126") (name "unconnected-(P67-Pad1)") (class "Default")
      (node (ref "P67") (pin "1") (pinfunction "1_1") (pintype "bidirectional"))
    )
    (net (code "127") (name "unconnected-(P68-Pad1)") (class "Default")
      (node (ref "P68") (pin "1") (pinfunction "1_1") (pintype "bidirectional"))
    )
    (net (code "128") (name "unconnected-(P69-Pad1)") (class "Default")
      (node (ref "P69") (pin "1") (pinfunction "1_1") (pintype "bidirectional"))
    )
    (net (code "129") (name "unconnected-(P70-Pad1)") (class "Default")
      (node (ref "P70") (pin "1") (pinfunction "1_1") (pintype "bidirectional"))
    )
    (net (code "130") (name "unconnected-(P71-Pad1)") (class "Default")
      (node (ref "P71") (pin "1") (pinfunction "1_1") (pintype "bidirectional"))
    )
    (net (code "131") (name "unconnected-(P72-Pad1)") (class "Default")
      (node (ref "P72") (pin "1") (pinfunction "1_1") (pintype "bidirectional"))
    )
    (net (code "132") (name "unconnected-(P73-Pad1)") (class "Default")
      (node (ref "P73") (pin "1") (pinfunction "1_1") (pintype "bidirectional"))
    )
    (net (code "133") (name "unconnected-(P74-Pad1)") (class "Default")
      (node (ref "P74") (pin "1") (pinfunction "1_1") (pintype "bidirectional"))
    )
    (net (code "134") (name "unconnected-(P75-Pad1)") (class "Default")
      (node (ref "P75") (pin "1") (pinfunction "1_1") (pintype "bidirectional"))
    )
    (net (code "135") (name "unconnected-(P76-Pad1)") (class "Default")
      (node (ref "P76") (pin "1") (pinfunction "1_1") (pintype "bidirectional"))
    )
    (net (code "136") (name "unconnected-(P77-Pad1)") (class "Default")
      (node (ref "P77") (pin "1") (pinfunction "1_1") (pintype "bidirectional"))
    )
    (net (code "137") (name "unconnected-(P78-Pad1)") (class "Default")
      (node (ref "P78") (pin "1") (pinfunction "1_1") (pintype "bidirectional"))
    )
    (net (code "138") (name "unconnected-(P79-Pad1)") (class "Default")
      (node (ref "P79") (pin "1") (pinfunction "1_1") (pintype "bidirectional"))
    )
    (net (code "139") (name "unconnected-(P80-Pad1)") (class "Default")
      (node (ref "P80") (pin "1") (pinfunction "1_1") (pintype "bidirectional"))
    )
    (net (code "140") (name "unconnected-(P81-Pad1)") (class "Default")
      (node (ref "P81") (pin "1") (pinfunction "1_1") (pintype "bidirectional"))
    )
    (net (code "141") (name "unconnected-(P82-Pad1)") (class "Default")
      (node (ref "P82") (pin "1") (pinfunction "1_1") (pintype "bidirectional"))
    )
    (net (code "142") (name "unconnected-(P83-Pad1)") (class "Default")
      (node (ref "P83") (pin "1") (pinfunction "1_1") (pintype "bidirectional"))
    )
    (net (code "143") (name "unconnected-(P84-Pad1)") (class "Default")
      (node (ref "P84") (pin "1") (pinfunction "1_1") (pintype "bidirectional"))
    )
    (net (code "144") (name "unconnected-(P85-Pad1)") (class "Default")
      (node (ref "P85") (pin "1") (pinfunction "1_1") (pintype "bidirectional"))
    )
    (net (code "145") (name "unconnected-(P86-Pad1)") (class "Default")
      (node (ref "P86") (pin "1") (pinfunction "1_1") (pintype "bidirectional"))
    )
    (net (code "146") (name "unconnected-(P87-Pad1)") (class "Default")
      (node (ref "P87") (pin "1") (pinfunction "1_1") (pintype "bidirectional"))
    )
    (net (code "147") (name "unconnected-(P88-Pad1)") (class "Default")
      (node (ref "P88") (pin "1") (pinfunction "1_1") (pintype "bidirectional"))
    )
    (net (code "148") (name "unconnected-(P89-Pad1)") (class "Default")
      (node (ref "P89") (pin "1") (pinfunction "1_1") (pintype "bidirectional"))
    )
    (net (code "149") (name "unconnected-(P90-Pad1)") (class "Default")
      (node (ref "P90") (pin "1") (pinfunction "1_1") (pintype "bidirectional"))
    )
    (net (code "150") (name "unconnected-(P91-Pad1)") (class "Default")
      (node (ref "P91") (pin "1") (pinfunction "1_1") (pintype "bidirectional"))
    )
    (net (code "151") (name "unconnected-(P92-Pad1)") (class "Default")
      (node (ref "P92") (pin "1") (pinfunction "1_1") (pintype "bidirectional"))
    )
    (net (code "152") (name "unconnected-(P93-Pad1)") (class "Default")
      (node (ref "P93") (pin "1") (pinfunction "1_1") (pintype "bidirectional"))
    )
    (net (code "153") (name "unconnected-(P94-Pad1)") (class "Default")
      (node (ref "P94") (pin "1") (pinfunction "1_1") (pintype "bidirectional"))
    )
    (net (code "154") (name "unconnected-(P95-Pad1)") (class "Default")
      (node (ref "P95") (pin "1") (pinfunction "1_1") (pintype "bidirectional"))
    )
    (net (code "155") (name "unconnected-(P96-Pad1)") (class "Default")
      (node (ref "P96") (pin "1") (pinfunction "1_1") (pintype "bidirectional"))
    )
    (net (code "156") (name "unconnected-(P97-Pad1)") (class "Default")
      (node (ref "P97") (pin "1") (pinfunction "1_1") (pintype "bidirectional"))
    )
    (net (code "157") (name "unconnected-(P98-Pad1)") (class "Default")
      (node (ref "P98") (pin "1") (pinfunction "1_1") (pintype "bidirectional"))
    )
    (net (code "158") (name "unconnected-(P99-Pad1)") (class "Default")
      (node (ref "P99") (pin "1") (pinfunction "1_1") (pintype "bidirectional"))
    )
    (net (code "159") (name "unconnected-(P100-Pad1)") (class "Default")
      (node (ref "P100") (pin "1") (pinfunction "1_1") (pintype "bidirectional"))
    )
    (net (code "160") (name "unconnected-(P101-Pad1)") (class "Default")
      (node (ref "P101") (pin "1") (pinfunction "1_1") (pintype "bidirectional"))
    )
    (net (code "161") (name "unconnected-(P104-Pad1)") (class "Default")
      (node (ref "P104") (pin "1") (pinfunction "1_1") (pintype "bidirectional"))
    )
    (net (code "162") (name "unconnected-(P105-Pad1)") (class "Default")
      (node (ref "P105") (pin "1") (pinfunction "1_1") (pintype "bidirectional"))
    )
    (net (code "163") (name "unconnected-(P106-Pad1)") (class "Default")
      (node (ref "P106") (pin "1") (pinfunction "1_1") (pintype "bidirectional"))
    )
    (net (code "164") (name "unconnected-(P107-Pad1)") (class "Default")
      (node (ref "P107") (pin "1") (pinfunction "1_1") (pintype "bidirectional"))
    )
    (net (code "165") (name "unconnected-(P108-Pad1)") (class "Default")
      (node (ref "P108") (pin "1") (pinfunction "1_1") (pintype "bidirectional"))
    )
    (net (code "166") (name "unconnected-(P109-Pad1)") (class "Default")
      (node (ref "P109") (pin "1") (pinfunction "1_1") (pintype "bidirectional"))
    )
    (net (code "167") (name "unconnected-(P110-Pad1)") (class "Default")
      (node (ref "P110") (pin "1") (pinfunction "1_1") (pintype "bidirectional"))
    )
    (net (code "168") (name "unconnected-(P111-Pad1)") (class "Default")
      (node (ref "P111") (pin "1") (pinfunction "1_1") (pintype "bidirectional"))
    )
    (net (code "169") (name "unconnected-(P112-Pad1)") (class "Default")
      (node (ref "P112") (pin "1") (pinfunction "1_1") (pintype "bidirectional"))
    )
    (net (code "170") (name "unconnected-(P113-Pad1)") (class "Default")
      (node (ref "P113") (pin "1") (pinfunction "1_1") (pintype "bidirectional"))
    )
    (net (code "171") (name "unconnected-(P115-Pad1)") (class "Default")
      (node (ref "P115") (pin "1") (pinfunction "1_1") (pintype "bidirectional"))
    )
    (net (code "172") (name "unconnected-(P116-Pad1)") (class "Default")
      (node (ref "P116") (pin "1") (pinfunction "1_1") (pintype "bidirectional"))
    )
    (net (code "173") (name "unconnected-(P117-Pad1)") (class "Default")
      (node (ref "P117") (pin "1") (pinfunction "1_1") (pintype "bidirectional"))
    )
    (net (code "174") (name "unconnected-(P118-Pad1)") (class "Default")
      (node (ref "P118") (pin "1") (pinfunction "1_1") (pintype "bidirectional"))
    )
    (net (code "175") (name "unconnected-(P119-Pad1)") (class "Default")
      (node (ref "P119") (pin "1") (pinfunction "1_1") (pintype "bidirectional"))
    )
    (net (code "176") (name "unconnected-(P120-Pad1)") (class "Default")
      (node (ref "P120") (pin "1") (pinfunction "1_1") (pintype "bidirectional"))
    )
    (net (code "177") (name "unconnected-(P121-Pad1)") (class "Default")
      (node (ref "P121") (pin "1") (pinfunction "1_1") (pintype "bidirectional"))
    )
    (net (code "178") (name "unconnected-(P122-Pad1)") (class "Default")
      (node (ref "P122") (pin "1") (pinfunction "1_1") (pintype "bidirectional"))
    )
    (net (code "179") (name "unconnected-(P123-Pad1)") (class "Default")
      (node (ref "P123") (pin "1") (pinfunction "1_1") (pintype "bidirectional"))
    )
    (net (code "180") (name "unconnected-(P124-Pad1)") (class "Default")
      (node (ref "P124") (pin "1") (pinfunction "1_1") (pintype "bidirectional"))
    )
    (net (code "181") (name "unconnected-(P125-Pad1)") (class "Default")
      (node (ref "P125") (pin "1") (pinfunction "1_1") (pintype "bidirectional"))
    )
    (net (code "182") (name "unconnected-(P126-Pad1)") (class "Default")
      (node (ref "P126") (pin "1") (pinfunction "1_1") (pintype "bidirectional"))
    )
    (net (code "183") (name "unconnected-(P127-Pad1)") (class "Default")
      (node (ref "P127") (pin "1") (pinfunction "1_1") (pintype "bidirectional"))
    )
    (net (code "184") (name "unconnected-(P128-Pad1)") (class "Default")
      (node (ref "P128") (pin "1") (pinfunction "1_1") (pintype "bidirectional"))
    )
    (net (code "185") (name "unconnected-(P129-Pad1)") (class "Default")
      (node (ref "P129") (pin "1") (pinfunction "1_1") (pintype "bidirectional"))
    )
    (net (code "186") (name "unconnected-(P130-Pad1)") (class "Default")
      (node (ref "P130") (pin "1") (pinfunction "1_1") (pintype "bidirectional"))
    )
    (net (code "187") (name "unconnected-(P131-Pad1)") (class "Default")
      (node (ref "P131") (pin "1") (pinfunction "1_1") (pintype "bidirectional"))
    )
    (net (code "188") (name "unconnected-(P132-Pad1)") (class "Default")
      (node (ref "P132") (pin "1") (pinfunction "1_1") (pintype "bidirectional"))
    )
    (net (code "189") (name "unconnected-(P133-Pad1)") (class "Default")
      (node (ref "P133") (pin "1") (pinfunction "1_1") (pintype "bidirectional"))
    )
    (net (code "190") (name "unconnected-(P134-Pad1)") (class "Default")
      (node (ref "P134") (pin "1") (pinfunction "1_1") (pintype "bidirectional"))
    )
    (net (code "191") (name "unconnected-(P135-Pad1)") (class "Default")
      (node (ref "P135") (pin "1") (pinfunction "1_1") (pintype "bidirectional"))
    )
    (net (code "192") (name "unconnected-(P136-Pad1)") (class "Default")
      (node (ref "P136") (pin "1") (pinfunction "1_1") (pintype "bidirectional"))
    )
    (net (code "193") (name "unconnected-(P137-Pad1)") (class "Default")
      (node (ref "P137") (pin "1") (pinfunction "1_1") (pintype "bidirectional"))
    )
    (net (code "194") (name "unconnected-(P138-Pad1)") (class "Default")
      (node (ref "P138") (pin "1") (pinfunction "1_1") (pintype "bidirectional"))
    )
    (net (code "195") (name "unconnected-(P139-Pad1)") (class "Default")
      (node (ref "P139") (pin "1") (pinfunction "1_1") (pintype "bidirectional"))
    )
    (net (code "196") (name "unconnected-(P140-Pad1)") (class "Default")
      (node (ref "P140") (pin "1") (pinfunction "1_1") (pintype "bidirectional"))
    )
    (net (code "197") (name "unconnected-(P141-Pad1)") (class "Default")
      (node (ref "P141") (pin "1") (pinfunction "1_1") (pintype "bidirectional"))
    )
    (net (code "198") (name "unconnected-(P142-Pad1)") (class "Default")
      (node (ref "P142") (pin "1") (pinfunction "1_1") (pintype "bidirectional"))
    )
    (net (code "199") (name "unconnected-(P143-Pad1)") (class "Default")
      (node (ref "P143") (pin "1") (pinfunction "1_1") (pintype "bidirectional"))
    )
    (net (code "200") (name "unconnected-(P144-Pad1)") (class "Default")
      (node (ref "P144") (pin "1") (pinfunction "1_1") (pintype "bidirectional"))
    )
    (net (code "201") (name "unconnected-(P145-Pad1)") (class "Default")
      (node (ref "P145") (pin "1") (pinfunction "1_1") (pintype "bidirectional"))
    )
    (net (code "202") (name "unconnected-(P146-Pad1)") (class "Default")
      (node (ref "P146") (pin "1") (pinfunction "1_1") (pintype "bidirectional"))
    )
    (net (code "203") (name "unconnected-(P147-Pad1)") (class "Default")
      (node (ref "P147") (pin "1") (pinfunction "1_1") (pintype "bidirectional"))
    )
    (net (code "204") (name "unconnected-(P148-Pad1)") (class "Default")
      (node (ref "P148") (pin "1") (pinfunction "1_1") (pintype "bidirectional"))
    )
    (net (code "205") (name "unconnected-(P149-Pad1)") (class "Default")
      (node (ref "P149") (pin "1") (pinfunction "1_1") (pintype "bidirectional"))
    )
    (net (code "206") (name "unconnected-(P150-Pad1)") (class "Default")
      (node (ref "P150") (pin "1") (pinfunction "1_1") (pintype "bidirectional"))
    )
    (net (code "207") (name "unconnected-(P151-Pad1)") (class "Default")
      (node (ref "P151") (pin "1") (pinfunction "1_1") (pintype "bidirectional"))
    )
    (net (code "208") (name "unconnected-(P152-Pad1)") (class "Default")
      (node (ref "P152") (pin "1") (pinfunction "1_1") (pintype "bidirectional"))
    )
    (net (code "209") (name "unconnected-(P153-Pad1)") (class "Default")
      (node (ref "P153") (pin "1") (pinfunction "1_1") (pintype "bidirectional"))
    )
    (net (code "210") (name "unconnected-(P154-Pad1)") (class "Default")
      (node (ref "P154") (pin "1") (pinfunction "1_1") (pintype "bidirectional"))
    )
    (net (code "211") (name "unconnected-(P155-Pad1)") (class "Default")
      (node (ref "P155") (pin "1") (pinfunction "1_1") (pintype "bidirectional"))
    )
    (net (code "212") (name "unconnected-(P156-Pad1)") (class "Default")
      (node (ref "P156") (pin "1") (pinfunction "1_1") (pintype "bidirectional"))
    )
    (net (code "213") (name "unconnected-(P157-Pad1)") (class "Default")
      (node (ref "P157") (pin "1") (pinfunction "1_1") (pintype "bidirectional"))
    )
    (net (code "214") (name "unconnected-(P158-Pad1)") (class "Default")
      (node (ref "P158") (pin "1") (pinfunction "1_1") (pintype "bidirectional"))
    )
    (net (code "215") (name "unconnected-(P159-Pad1)") (class "Default")
      (node (ref "P159") (pin "1") (pinfunction "1_1") (pintype "bidirectional"))
    )
    (net (code "216") (name "unconnected-(P160-Pad1)") (class "Default")
      (node (ref "P160") (pin "1") (pinfunction "1_1") (pintype "bidirectional"))
    )
    (net (code "217") (name "unconnected-(P161-Pad1)") (class "Default")
      (node (ref "P161") (pin "1") (pinfunction "1_1") (pintype "bidirectional"))
    )
    (net (code "218") (name "unconnected-(P162-Pad1)") (class "Default")
      (node (ref "P162") (pin "1") (pinfunction "1_1") (pintype "bidirectional"))
    )
    (net (code "219") (name "unconnected-(P163-Pad1)") (class "Default")
      (node (ref "P163") (pin "1") (pinfunction "1_1") (pintype "bidirectional"))
    )
    (net (code "220") (name "unconnected-(P164-Pad1)") (class "Default")
      (node (ref "P164") (pin "1") (pinfunction "1_1") (pintype "bidirectional"))
    )
    (net (code "221") (name "unconnected-(P165-Pad1)") (class "Default")
      (node (ref "P165") (pin "1") (pinfunction "1_1") (pintype "bidirectional"))
    )
    (net (code "222") (name "unconnected-(P166-Pad1)") (class "Default")
      (node (ref "P166") (pin "1") (pinfunction "1_1") (pintype "bidirectional"))
    )
    (net (code "223") (name "unconnected-(P167-Pad1)") (class "Default")
      (node (ref "P167") (pin "1") (pinfunction "1_1") (pintype "bidirectional"))
    )
    (net (code "224") (name "unconnected-(P168-Pad1)") (class "Default")
      (node (ref "P168") (pin "1") (pinfunction "1_1") (pintype "bidirectional"))
    )
    (net (code "225") (name "unconnected-(P169-Pad1)") (class "Default")
      (node (ref "P169") (pin "1") (pinfunction "1_1") (pintype "bidirectional"))
    )
    (net (code "226") (name "unconnected-(P170-Pad1)") (class "Default")
      (node (ref "P170") (pin "1") (pinfunction "1_1") (pintype "bidirectional"))
    )
    (net (code "227") (name "unconnected-(P171-Pad1)") (class "Default")
      (node (ref "P171") (pin "1") (pinfunction "1_1") (pintype "bidirectional"))
    )
    (net (code "228") (name "unconnected-(P172-Pad1)") (class "Default")
      (node (ref "P172") (pin "1") (pinfunction "1_1") (pintype "bidirectional"))
    )
    (net (code "229") (name "unconnected-(P173-Pad1)") (class "Default")
      (node (ref "P173") (pin "1") (pinfunction "1_1") (pintype "bidirectional"))
    )
    (net (code "230") (name "unconnected-(P174-Pad1)") (class "Default")
      (node (ref "P174") (pin "1") (pinfunction "1_1") (pintype "bidirectional"))
    )
    (net (code "231") (name "unconnected-(P175-Pad1)") (class "Default")
      (node (ref "P175") (pin "1") (pinfunction "1_1") (pintype "bidirectional"))
    )
    (net (code "232") (name "unconnected-(P176-Pad1)") (class "Default")
      (node (ref "P176") (pin "1") (pinfunction "1_1") (pintype "bidirectional"))
    )
    (net (code "233") (name "unconnected-(P177-Pad1)") (class "Default")
      (node (ref "P177") (pin "1") (pinfunction "1_1") (pintype "bidirectional"))
    )
    (net (code "234") (name "unconnected-(P178-Pad1)") (class "Default")
      (node (ref "P178") (pin "1") (pinfunction "1_1") (pintype "bidirectional"))
    )
    (net (code "235") (name "unconnected-(P179-Pad1)") (class "Default")
      (node (ref "P179") (pin "1") (pinfunction "1_1") (pintype "bidirectional"))
    )
    (net (code "236") (name "unconnected-(P180-Pad1)") (class "Default")
      (node (ref "P180") (pin "1") (pinfunction "1_1") (pintype "bidirectional"))
    )
    (net (code "237") (name "unconnected-(P181-Pad1)") (class "Default")
      (node (ref "P181") (pin "1") (pinfunction "1_1") (pintype "bidirectional"))
    )
    (net (code "238") (name "unconnected-(P182-Pad1)") (class "Default")
      (node (ref "P182") (pin "1") (pinfunction "1_1") (pintype "bidirectional"))
    )
    (net (code "239") (name "unconnected-(P183-Pad1)") (class "Default")
      (node (ref "P183") (pin "1") (pinfunction "1_1") (pintype "bidirectional"))
    )
    (net (code "240") (name "unconnected-(P184-Pad1)") (class "Default")
      (node (ref "P184") (pin "1") (pinfunction "1_1") (pintype "bidirectional"))
    )
    (net (code "241") (name "unconnected-(P185-Pad1)") (class "Default")
      (node (ref "P185") (pin "1") (pinfunction "1_1") (pintype "bidirectional"))
    )
    (net (code "242") (name "unconnected-(P186-Pad1)") (class "Default")
      (node (ref "P186") (pin "1") (pinfunction "1_1") (pintype "bidirectional"))
    )
    (net (code "243") (name "unconnected-(P187-Pad1)") (class "Default")
      (node (ref "P187") (pin "1") (pinfunction "1_1") (pintype "bidirectional"))
    )
    (net (code "244") (name "unconnected-(P188-Pad1)") (class "Default")
      (node (ref "P188") (pin "1") (pinfunction "1_1") (pintype "bidirectional"))
    )
    (net (code "245") (name "unconnected-(P189-Pad1)") (class "Default")
      (node (ref "P189") (pin "1") (pinfunction "1_1") (pintype "bidirectional"))
    )
    (net (code "246") (name "unconnected-(P190-Pad1)") (class "Default")
      (node (ref "P190") (pin "1") (pinfunction "1_1") (pintype "bidirectional"))
    )
    (net (code "247") (name "unconnected-(P191-Pad1)") (class "Default")
      (node (ref "P191") (pin "1") (pinfunction "1_1") (pintype "bidirectional"))
    )
    (net (code "248") (name "unconnected-(P192-Pad1)") (class "Default")
      (node (ref "P192") (pin "1") (pinfunction "1_1") (pintype "bidirectional"))
    )
    (net (code "249") (name "unconnected-(P193-Pad1)") (class "Default")
      (node (ref "P193") (pin "1") (pinfunction "1_1") (pintype "bidirectional"))
    )
    (net (code "250") (name "unconnected-(P194-Pad1)") (class "Default")
      (node (ref "P194") (pin "1") (pinfunction "1_1") (pintype "bidirectional"))
    )
    (net (code "251") (name "unconnected-(P195-Pad1)") (class "Default")
      (node (ref "P195") (pin "1") (pinfunction "1_1") (pintype "bidirectional"))
    )
    (net (code "252") (name "unconnected-(P196-Pad1)") (class "Default")
      (node (ref "P196") (pin "1") (pinfunction "1_1") (pintype "bidirectional"))
    )
    (net (code "253") (name "unconnected-(P197-Pad1)") (class "Default")
      (node (ref "P197") (pin "1") (pinfunction "1_1") (pintype "bidirectional"))
    )
    (net (code "254") (name "unconnected-(P198-Pad1)") (class "Default")
      (node (ref "P198") (pin "1") (pinfunction "1_1") (pintype "bidirectional"))
    )
    (net (code "255") (name "unconnected-(P199-Pad1)") (class "Default")
      (node (ref "P199") (pin "1") (pinfunction "1_1") (pintype "bidirectional"))
    )
    (net (code "256") (name "unconnected-(P200-Pad1)") (class "Default")
      (node (ref "P200") (pin "1") (pinfunction "1_1") (pintype "bidirectional"))
    )
    (net (code "257") (name "unconnected-(P201-Pad1)") (class "Default")
      (node (ref "P201") (pin "1") (pinfunction "1_1") (pintype "bidirectional"))
    )
    (net (code "258") (name "unconnected-(P202-Pad1)") (class "Default")
      (node (ref "P202") (pin "1") (pinfunction "1_1") (pintype "bidirectional"))
    )
    (net (code "259") (name "unconnected-(P203-Pad1)") (class "Default")
      (node (ref "P203") (pin "1") (pinfunction "1_1") (pintype "bidirectional"))
    )
    (net (code "260") (name "unconnected-(P204-Pad1)") (class "Default")
      (node (ref "P204") (pin "1") (pinfunction "1_1") (pintype "bidirectional"))
    )
    (net (code "261") (name "unconnected-(P205-Pad1)") (class "Default")
      (node (ref "P205") (pin "1") (pinfunction "1_1") (pintype "bidirectional"))
    )
    (net (code "262") (name "unconnected-(P206-Pad1)") (class "Default")
      (node (ref "P206") (pin "1") (pinfunction "1_1") (pintype "bidirectional"))
    )
    (net (code "263") (name "unconnected-(P207-Pad1)") (class "Default")
      (node (ref "P207") (pin "1") (pinfunction "1_1") (pintype "bidirectional"))
    )
    (net (code "264") (name "unconnected-(P208-Pad1)") (class "Default")
      (node (ref "P208") (pin "1") (pinfunction "1_1") (pintype "bidirectional"))
    )
    (net (code "265") (name "unconnected-(P209-Pad1)") (class "Default")
      (node (ref "P209") (pin "1") (pinfunction "1_1") (pintype "bidirectional"))
    )
    (net (code "266") (name "unconnected-(P210-Pad1)") (class "Default")
      (node (ref "P210") (pin "1") (pinfunction "1_1") (pintype "bidirectional"))
    )
    (net (code "267") (name "unconnected-(P211-Pad1)") (class "Default")
      (node (ref "P211") (pin "1") (pinfunction "1_1") (pintype "bidirectional"))
    )
    (net (code "268") (name "unconnected-(P212-Pad1)") (class "Default")
      (node (ref "P212") (pin "1") (pinfunction "1_1") (pintype "bidirectional"))
    )
    (net (code "269") (name "unconnected-(P213-Pad1)") (class "Default")
      (node (ref "P213") (pin "1") (pinfunction "1_1") (pintype "bidirectional"))
    )
    (net (code "270") (name "unconnected-(P214-Pad1)") (class "Default")
      (node (ref "P214") (pin "1") (pinfunction "1_1") (pintype "bidirectional"))
    )
    (net (code "271") (name "unconnected-(P215-Pad1)") (class "Default")
      (node (ref "P215") (pin "1") (pinfunction "1_1") (pintype "bidirectional"))
    )
    (net (code "272") (name "unconnected-(P216-Pad1)") (class "Default")
      (node (ref "P216") (pin "1") (pinfunction "1_1") (pintype "bidirectional"))
    )
    (net (code "273") (name "unconnected-(P217-Pad1)") (class "Default")
      (node (ref "P217") (pin "1") (pinfunction "1_1") (pintype "bidirectional"))
    )
    (net (code "274") (name "unconnected-(P218-Pad1)") (class "Default")
      (node (ref "P218") (pin "1") (pinfunction "1_1") (pintype "bidirectional"))
    )
    (net (code "275") (name "unconnected-(P219-Pad1)") (class "Default")
      (node (ref "P219") (pin "1") (pinfunction "1_1") (pintype "bidirectional"))
    )
    (net (code "276") (name "unconnected-(P220-Pad1)") (class "Default")
      (node (ref "P220") (pin "1") (pinfunction "1_1") (pintype "bidirectional"))
    )
    (net (code "277") (name "unconnected-(P221-Pad1)") (class "Default")
      (node (ref "P221") (pin "1") (pinfunction "1_1") (pintype "bidirectional"))
    )
    (net (code "278") (name "unconnected-(P222-Pad1)") (class "Default")
      (node (ref "P222") (pin "1") (pinfunction "1_1") (pintype "bidirectional"))
    )
    (net (code "279") (name "unconnected-(P223-Pad1)") (class "Default")
      (node (ref "P223") (pin "1") (pinfunction "1_1") (pintype "bidirectional"))
    )
    (net (code "280") (name "unconnected-(P224-Pad1)") (class "Default")
      (node (ref "P224") (pin "1") (pinfunction "1_1") (pintype "bidirectional"))
    )
    (net (code "281") (name "unconnected-(P225-Pad1)") (class "Default")
      (node (ref "P225") (pin "1") (pinfunction "1_1") (pintype "bidirectional"))
    )
    (net (code "282") (name "unconnected-(P226-Pad1)") (class "Default")
      (node (ref "P226") (pin "1") (pinfunction "1_1") (pintype "bidirectional"))
    )
    (net (code "283") (name "unconnected-(P227-Pad1)") (class "Default")
      (node (ref "P227") (pin "1") (pinfunction "1_1") (pintype "bidirectional"))
    )
    (net (code "284") (name "unconnected-(P228-Pad1)") (class "Default")
      (node (ref "P228") (pin "1") (pinfunction "1_1") (pintype "bidirectional"))
    )
    (net (code "285") (name "unconnected-(P229-Pad1)") (class "Default")
      (node (ref "P229") (pin "1") (pinfunction "1_1") (pintype "bidirectional"))
    )
    (net (code "286") (name "unconnected-(P230-Pad1)") (class "Default")
      (node (ref "P230") (pin "1") (pinfunction "1_1") (pintype "bidirectional"))
    )
    (net (code "287") (name "unconnected-(P231-Pad1)") (class "Default")
      (node (ref "P231") (pin "1") (pinfunction "1_1") (pintype "bidirectional"))
    )
    (net (code "288") (name "unconnected-(P232-Pad1)") (class "Default")
      (node (ref "P232") (pin "1") (pinfunction "1_1") (pintype "bidirectional"))
    )
    (net (code "289") (name "unconnected-(P233-Pad1)") (class "Default")
      (node (ref "P233") (pin "1") (pinfunction "1_1") (pintype "bidirectional"))
    )
    (net (code "290") (name "unconnected-(P234-Pad1)") (class "Default")
      (node (ref "P234") (pin "1") (pinfunction "1_1") (pintype "bidirectional"))
    )
    (net (code "291") (name "unconnected-(P235-Pad1)") (class "Default")
      (node (ref "P235") (pin "1") (pinfunction "1_1") (pintype "bidirectional"))
    )
    (net (code "292") (name "unconnected-(P236-Pad1)") (class "Default")
      (node (ref "P236") (pin "1") (pinfunction "1_1") (pintype "bidirectional"))
    )
    (net (code "293") (name "unconnected-(P237-Pad1)") (class "Default")
      (node (ref "P237") (pin "1") (pinfunction "1_1") (pintype "bidirectional"))
    )
    (net (code "294") (name "unconnected-(P238-Pad1)") (class "Default")
      (node (ref "P238") (pin "1") (pinfunction "1_1") (pintype "bidirectional"))
    )
    (net (code "295") (name "unconnected-(P239-Pad1)") (class "Default")
      (node (ref "P239") (pin "1") (pinfunction "1_1") (pintype "bidirectional"))
    )
    (net (code "296") (name "unconnected-(P240-Pad1)") (class "Default")
      (node (ref "P240") (pin "1") (pinfunction "1_1") (pintype "bidirectional"))
    )
    (net (code "297") (name "unconnected-(P241-Pad1)") (class "Default")
      (node (ref "P241") (pin "1") (pinfunction "1_1") (pintype "bidirectional"))
    )
    (net (code "298") (name "unconnected-(P242-Pad1)") (class "Default")
      (node (ref "P242") (pin "1") (pinfunction "1_1") (pintype "bidirectional"))
    )
    (net (code "299") (name "unconnected-(P243-Pad1)") (class "Default")
      (node (ref "P243") (pin "1") (pinfunction "1_1") (pintype "bidirectional"))
    )
    (net (code "300") (name "unconnected-(P244-Pad1)") (class "Default")
      (node (ref "P244") (pin "1") (pinfunction "1_1") (pintype "bidirectional"))
    )
    (net (code "301") (name "unconnected-(P245-Pad1)") (class "Default")
      (node (ref "P245") (pin "1") (pinfunction "1_1") (pintype "bidirectional"))
    )
    (net (code "302") (name "unconnected-(P246-Pad1)") (class "Default")
      (node (ref "P246") (pin "1") (pinfunction "1_1") (pintype "bidirectional"))
    )
    (net (code "303") (name "unconnected-(P247-Pad1)") (class "Default")
      (node (ref "P247") (pin "1") (pinfunction "1_1") (pintype "bidirectional"))
    )
    (net (code "304") (name "unconnected-(P248-Pad1)") (class "Default")
      (node (ref "P248") (pin "1") (pinfunction "1_1") (pintype "bidirectional"))
    )
    (net (code "305") (name "unconnected-(P249-Pad1)") (class "Default")
      (node (ref "P249") (pin "1") (pinfunction "1_1") (pintype "bidirectional"))
    )
    (net (code "306") (name "unconnected-(P250-Pad1)") (class "Default")
      (node (ref "P250") (pin "1") (pinfunction "1_1") (pintype "bidirectional"))
    )
    (net (code "307") (name "unconnected-(P251-Pad1)") (class "Default")
      (node (ref "P251") (pin "1") (pinfunction "1_1") (pintype "bidirectional"))
    )
    (net (code "308") (name "unconnected-(P252-Pad1)") (class "Default")
      (node (ref "P252") (pin "1") (pinfunction "1_1") (pintype "bidirectional"))
    )
    (net (code "309") (name "unconnected-(P253-Pad1)") (class "Default")
      (node (ref "P253") (pin "1") (pinfunction "1_1") (pintype "bidirectional"))
    )
    (net (code "310") (name "unconnected-(P254-Pad1)") (class "Default")
      (node (ref "P254") (pin "1") (pinfunction "1_1") (pintype "bidirectional"))
    )
    (net (code "311") (name "unconnected-(P255-Pad1)") (class "Default")
      (node (ref "P255") (pin "1") (pinfunction "1_1") (pintype "bidirectional"))
    )
    (net (code "312") (name "unconnected-(P256-Pad1)") (class "Default")
      (node (ref "P256") (pin "1") (pinfunction "1_1") (pintype "bidirectional"))
    )
    (net (code "313") (name "unconnected-(P257-Pad1)") (class "Default")
      (node (ref "P257") (pin "1") (pinfunction "1_1") (pintype "bidirectional"))
    )
    (net (code "314") (name "unconnected-(P258-Pad1)") (class "Default")
      (node (ref "P258") (pin "1") (pinfunction "1_1") (pintype "bidirectional"))
    )
    (net (code "315") (name "unconnected-(P259-Pad1)") (class "Default")
      (node (ref "P259") (pin "1") (pinfunction "1_1") (pintype "bidirectional"))
    )
    (net (code "316") (name "unconnected-(P260-Pad1)") (class "Default")
      (node (ref "P260") (pin "1") (pinfunction "1_1") (pintype "bidirectional"))
    )
    (net (code "317") (name "unconnected-(P261-Pad1)") (class "Default")
      (node (ref "P261") (pin "1") (pinfunction "1_1") (pintype "bidirectional"))
    )
    (net (code "318") (name "unconnected-(P262-Pad1)") (class "Default")
      (node (ref "P262") (pin "1") (pinfunction "1_1") (pintype "bidirectional"))
    )
    (net (code "319") (name "unconnected-(P263-Pad1)") (class "Default")
      (node (ref "P263") (pin "1") (pinfunction "1_1") (pintype "bidirectional"))
    )
    (net (code "320") (name "unconnected-(P264-Pad1)") (class "Default")
      (node (ref "P264") (pin "1") (pinfunction "1_1") (pintype "bidirectional"))
    )
    (net (code "321") (name "unconnected-(P265-Pad1)") (class "Default")
      (node (ref "P265") (pin "1") (pinfunction "1_1") (pintype "bidirectional"))
    )
    (net (code "322") (name "unconnected-(P266-Pad1)") (class "Default")
      (node (ref "P266") (pin "1") (pinfunction "1_1") (pintype "bidirectional"))
    )
    (net (code "323") (name "unconnected-(P267-Pad1)") (class "Default")
      (node (ref "P267") (pin "1") (pinfunction "1_1") (pintype "bidirectional"))
    )
    (net (code "324") (name "unconnected-(P268-Pad1)") (class "Default")
      (node (ref "P268") (pin "1") (pinfunction "1_1") (pintype "bidirectional"))
    )
    (net (code "325") (name "unconnected-(P269-Pad1)") (class "Default")
      (node (ref "P269") (pin "1") (pinfunction "1_1") (pintype "bidirectional"))
    )
    (net (code "326") (name "unconnected-(P270-Pad1)") (class "Default")
      (node (ref "P270") (pin "1") (pinfunction "1_1") (pintype "bidirectional"))
    )
    (net (code "327") (name "unconnected-(P271-Pad1)") (class "Default")
      (node (ref "P271") (pin "1") (pinfunction "1_1") (pintype "bidirectional"))
    )
    (net (code "328") (name "unconnected-(P272-Pad1)") (class "Default")
      (node (ref "P272") (pin "1") (pinfunction "1_1") (pintype "bidirectional"))
    )
    (net (code "329") (name "unconnected-(P273-Pad1)") (class "Default")
      (node (ref "P273") (pin "1") (pinfunction "1_1") (pintype "bidirectional"))
    )
    (net (code "330") (name "unconnected-(P274-Pad1)") (class "Default")
      (node (ref "P274") (pin "1") (pinfunction "1_1") (pintype "bidirectional"))
    )
    (net (code "331") (name "unconnected-(P275-Pad1)") (class "Default")
      (node (ref "P275") (pin "1") (pinfunction "1_1") (pintype "bidirectional"))
    )
    (net (code "332") (name "unconnected-(P276-Pad1)") (class "Default")
      (node (ref "P276") (pin "1") (pinfunction "1_1") (pintype "bidirectional"))
    )
    (net (code "333") (name "unconnected-(P277-Pad1)") (class "Default")
      (node (ref "P277") (pin "1") (pinfunction "1_1") (pintype "bidirectional"))
    )
    (net (code "334") (name "unconnected-(P278-Pad1)") (class "Default")
      (node (ref "P278") (pin "1") (pinfunction "1_1") (pintype "bidirectional"))
    )
    (net (code "335") (name "unconnected-(P279-Pad1)") (class "Default")
      (node (ref "P279") (pin "1") (pinfunction "1_1") (pintype "bidirectional"))
    )
    (net (code "336") (name "unconnected-(P280-Pad1)") (class "Default")
      (node (ref "P280") (pin "1") (pinfunction "1_1") (pintype "bidirectional"))
    )
    (net (code "337") (name "unconnected-(P281-Pad1)") (class "Default")
      (node (ref "P281") (pin "1") (pinfunction "1_1") (pintype "bidirectional"))
    )
    (net (code "338") (name "unconnected-(P282-Pad1)") (class "Default")
      (node (ref "P282") (pin "1") (pinfunction "1_1") (pintype "bidirectional"))
    )
    (net (code "339") (name "unconnected-(P283-Pad1)") (class "Default")
      (node (ref "P283") (pin "1") (pinfunction "1_1") (pintype "bidirectional"))
    )
    (net (code "340") (name "unconnected-(P284-Pad1)") (class "Default")
      (node (ref "P284") (pin "1") (pinfunction "1_1") (pintype "bidirectional"))
    )
    (net (code "341") (name "unconnected-(P285-Pad1)") (class "Default")
      (node (ref "P285") (pin "1") (pinfunction "1_1") (pintype "bidirectional"))
    )
    (net (code "342") (name "unconnected-(P286-Pad1)") (class "Default")
      (node (ref "P286") (pin "1") (pinfunction "1_1") (pintype "bidirectional"))
    )
    (net (code "343") (name "unconnected-(P287-Pad1)") (class "Default")
      (node (ref "P287") (pin "1") (pinfunction "1_1") (pintype "bidirectional"))
    )
    (net (code "344") (name "unconnected-(P288-Pad1)") (class "Default")
      (node (ref "P288") (pin "1") (pinfunction "1_1") (pintype "bidirectional"))
    )
    (net (code "345") (name "unconnected-(P289-Pad1)") (class "Default")
      (node (ref "P289") (pin "1") (pinfunction "1_1") (pintype "bidirectional"))
    )
    (net (code "346") (name "unconnected-(P290-Pad1)") (class "Default")
      (node (ref "P290") (pin "1") (pinfunction "1_1") (pintype "bidirectional"))
    )
    (net (code "347") (name "unconnected-(P291-Pad1)") (class "Default")
      (node (ref "P291") (pin "1") (pinfunction "1_1") (pintype "bidirectional"))
    )
    (net (code "348") (name "unconnected-(P292-Pad1)") (class "Default")
      (node (ref "P292") (pin "1") (pinfunction "1_1") (pintype "bidirectional"))
    )
    (net (code "349") (name "unconnected-(P293-Pad1)") (class "Default")
      (node (ref "P293") (pin "1") (pinfunction "1_1") (pintype "bidirectional"))
    )
    (net (code "350") (name "unconnected-(P294-Pad1)") (class "Default")
      (node (ref "P294") (pin "1") (pinfunction "1_1") (pintype "bidirectional"))
    )
    (net (code "351") (name "unconnected-(P295-Pad1)") (class "Default")
      (node (ref "P295") (pin "1") (pinfunction "1_1") (pintype "bidirectional"))
    )
    (net (code "352") (name "unconnected-(P296-Pad1)") (class "Default")
      (node (ref "P296") (pin "1") (pinfunction "1_1") (pintype "bidirectional"))
    )
    (net (code "353") (name "unconnected-(P297-Pad1)") (class "Default")
      (node (ref "P297") (pin "1") (pinfunction "1_1") (pintype "bidirectional"))
    )
    (net (code "354") (name "unconnected-(P298-Pad1)") (class "Default")
      (node (ref "P298") (pin "1") (pinfunction "1_1") (pintype "bidirectional"))
    )
    (net (code "355") (name "unconnected-(P299-Pad1)") (class "Default")
      (node (ref "P299") (pin "1") (pinfunction "1_1") (pintype "bidirectional"))
    )
    (net (code "356") (name "unconnected-(P300-Pad1)") (class "Default")
      (node (ref "P300") (pin "1") (pinfunction "1_1") (pintype "bidirectional"))
    )
    (net (code "357") (name "unconnected-(P301-Pad1)") (class "Default")
      (node (ref "P301") (pin "1") (pinfunction "1_1") (pintype "bidirectional"))
    )
    (net (code "358") (name "unconnected-(P302-Pad1)") (class "Default")
      (node (ref "P302") (pin "1") (pinfunction "1_1") (pintype "bidirectional"))
    )
    (net (code "359") (name "unconnected-(P303-Pad1)") (class "Default")
      (node (ref "P303") (pin "1") (pinfunction "1_1") (pintype "bidirectional"))
    )
    (net (code "360") (name "unconnected-(P304-Pad1)") (class "Default")
      (node (ref "P304") (pin "1") (pinfunction "1_1") (pintype "bidirectional"))
    )
    (net (code "361") (name "unconnected-(P305-Pad1)") (class "Default")
      (node (ref "P305") (pin "1") (pinfunction "1_1") (pintype "bidirectional"))
    )
    (net (code "362") (name "unconnected-(P306-Pad1)") (class "Default")
      (node (ref "P306") (pin "1") (pinfunction "1_1") (pintype "bidirectional"))
    )
    (net (code "363") (name "unconnected-(P307-Pad1)") (class "Default")
      (node (ref "P307") (pin "1") (pinfunction "1_1") (pintype "bidirectional"))
    )
    (net (code "364") (name "unconnected-(P308-Pad1)") (class "Default")
      (node (ref "P308") (pin "1") (pinfunction "1_1") (pintype "bidirectional"))
    )
    (net (code "365") (name "unconnected-(P309-Pad1)") (class "Default")
      (node (ref "P309") (pin "1") (pinfunction "1_1") (pintype "bidirectional"))
    )
    (net (code "366") (name "unconnected-(P310-Pad1)") (class "Default")
      (node (ref "P310") (pin "1") (pinfunction "1_1") (pintype "bidirectional"))
    )
    (net (code "367") (name "unconnected-(P311-Pad1)") (class "Default")
      (node (ref "P311") (pin "1") (pinfunction "1_1") (pintype "bidirectional"))
    )
    (net (code "368") (name "unconnected-(P312-Pad1)") (class "Default")
      (node (ref "P312") (pin "1") (pinfunction "1_1") (pintype "bidirectional"))
    )
    (net (code "369") (name "unconnected-(P313-Pad1)") (class "Default")
      (node (ref "P313") (pin "1") (pinfunction "1_1") (pintype "bidirectional"))
    )
    (net (code "370") (name "unconnected-(P314-Pad1)") (class "Default")
      (node (ref "P314") (pin "1") (pinfunction "1_1") (pintype "bidirectional"))
    )
    (net (code "371") (name "unconnected-(P315-Pad1)") (class "Default")
      (node (ref "P315") (pin "1") (pinfunction "1_1") (pintype "bidirectional"))
    )
    (net (code "372") (name "unconnected-(P316-Pad1)") (class "Default")
      (node (ref "P316") (pin "1") (pinfunction "1_1") (pintype "bidirectional"))
    )
    (net (code "373") (name "unconnected-(P317-Pad1)") (class "Default")
      (node (ref "P317") (pin "1") (pinfunction "1_1") (pintype "bidirectional"))
    )
    (net (code "374") (name "unconnected-(P318-Pad1)") (class "Default")
      (node (ref "P318") (pin "1") (pinfunction "1_1") (pintype "bidirectional"))
    )
    (net (code "375") (name "unconnected-(P319-Pad1)") (class "Default")
      (node (ref "P319") (pin "1") (pinfunction "1_1") (pintype "bidirectional"))
    )
    (net (code "376") (name "unconnected-(P320-Pad1)") (class "Default")
      (node (ref "P320") (pin "1") (pinfunction "1_1") (pintype "bidirectional"))
    )
    (net (code "377") (name "unconnected-(P321-Pad1)") (class "Default")
      (node (ref "P321") (pin "1") (pinfunction "1_1") (pintype "bidirectional"))
    )
    (net (code "378") (name "unconnected-(P322-Pad1)") (class "Default")
      (node (ref "P322") (pin "1") (pinfunction "1_1") (pintype "bidirectional"))
    )
    (net (code "379") (name "unconnected-(P323-Pad1)") (class "Default")
      (node (ref "P323") (pin "1") (pinfunction "1_1") (pintype "bidirectional"))
    )
    (net (code "380") (name "unconnected-(P324-Pad1)") (class "Default")
      (node (ref "P324") (pin "1") (pinfunction "1_1") (pintype "bidirectional"))
    )
    (net (code "381") (name "unconnected-(P325-Pad1)") (class "Default")
      (node (ref "P325") (pin "1") (pinfunction "1_1") (pintype "bidirectional"))
    )
    (net (code "382") (name "unconnected-(P326-Pad1)") (class "Default")
      (node (ref "P326") (pin "1") (pinfunction "1_1") (pintype "bidirectional"))
    )
    (net (code "383") (name "unconnected-(P327-Pad1)") (class "Default")
      (node (ref "P327") (pin "1") (pinfunction "1_1") (pintype "bidirectional"))
    )
    (net (code "384") (name "unconnected-(P328-Pad1)") (class "Default")
      (node (ref "P328") (pin "1") (pinfunction "1_1") (pintype "bidirectional"))
    )
    (net (code "385") (name "unconnected-(P329-Pad1)") (class "Default")
      (node (ref "P329") (pin "1") (pinfunction "1_1") (pintype "bidirectional"))
    )
    (net (code "386") (name "unconnected-(P330-Pad1)") (class "Default")
      (node (ref "P330") (pin "1") (pinfunction "1_1") (pintype "bidirectional"))
    )
    (net (code "387") (name "unconnected-(P331-Pad1)") (class "Default")
      (node (ref "P331") (pin "1") (pinfunction "1_1") (pintype "bidirectional"))
    )
    (net (code "388") (name "unconnected-(P332-Pad1)") (class "Default")
      (node (ref "P332") (pin "1") (pinfunction "1_1") (pintype "bidirectional"))
    )
    (net (code "389") (name "unconnected-(P333-Pad1)") (class "Default")
      (node (ref "P333") (pin "1") (pinfunction "1_1") (pintype "bidirectional"))
    )
    (net (code "390") (name "unconnected-(P334-Pad1)") (class "Default")
      (node (ref "P334") (pin "1") (pinfunction "1_1") (pintype "bidirectional"))
    )
    (net (code "391") (name "unconnected-(P335-Pad1)") (class "Default")
      (node (ref "P335") (pin "1") (pinfunction "1_1") (pintype "bidirectional"))
    )
    (net (code "392") (name "unconnected-(P336-Pad1)") (class "Default")
      (node (ref "P336") (pin "1") (pinfunction "1_1") (pintype "bidirectional"))
    )
    (net (code "393") (name "unconnected-(P337-Pad1)") (class "Default")
      (node (ref "P337") (pin "1") (pinfunction "1_1") (pintype "bidirectional"))
    )
    (net (code "394") (name "unconnected-(P338-Pad1)") (class "Default")
      (node (ref "P338") (pin "1") (pinfunction "1_1") (pintype "bidirectional"))
    )
    (net (code "395") (name "unconnected-(P339-Pad1)") (class "Default")
      (node (ref "P339") (pin "1") (pinfunction "1_1") (pintype "bidirectional"))
    )
    (net (code "396") (name "unconnected-(P340-Pad1)") (class "Default")
      (node (ref "P340") (pin "1") (pinfunction "1_1") (pintype "bidirectional"))
    )
  )
)
